# lupa-hdmi-carrier.net
KiCad netlist of a schematic drawn in EAGLE
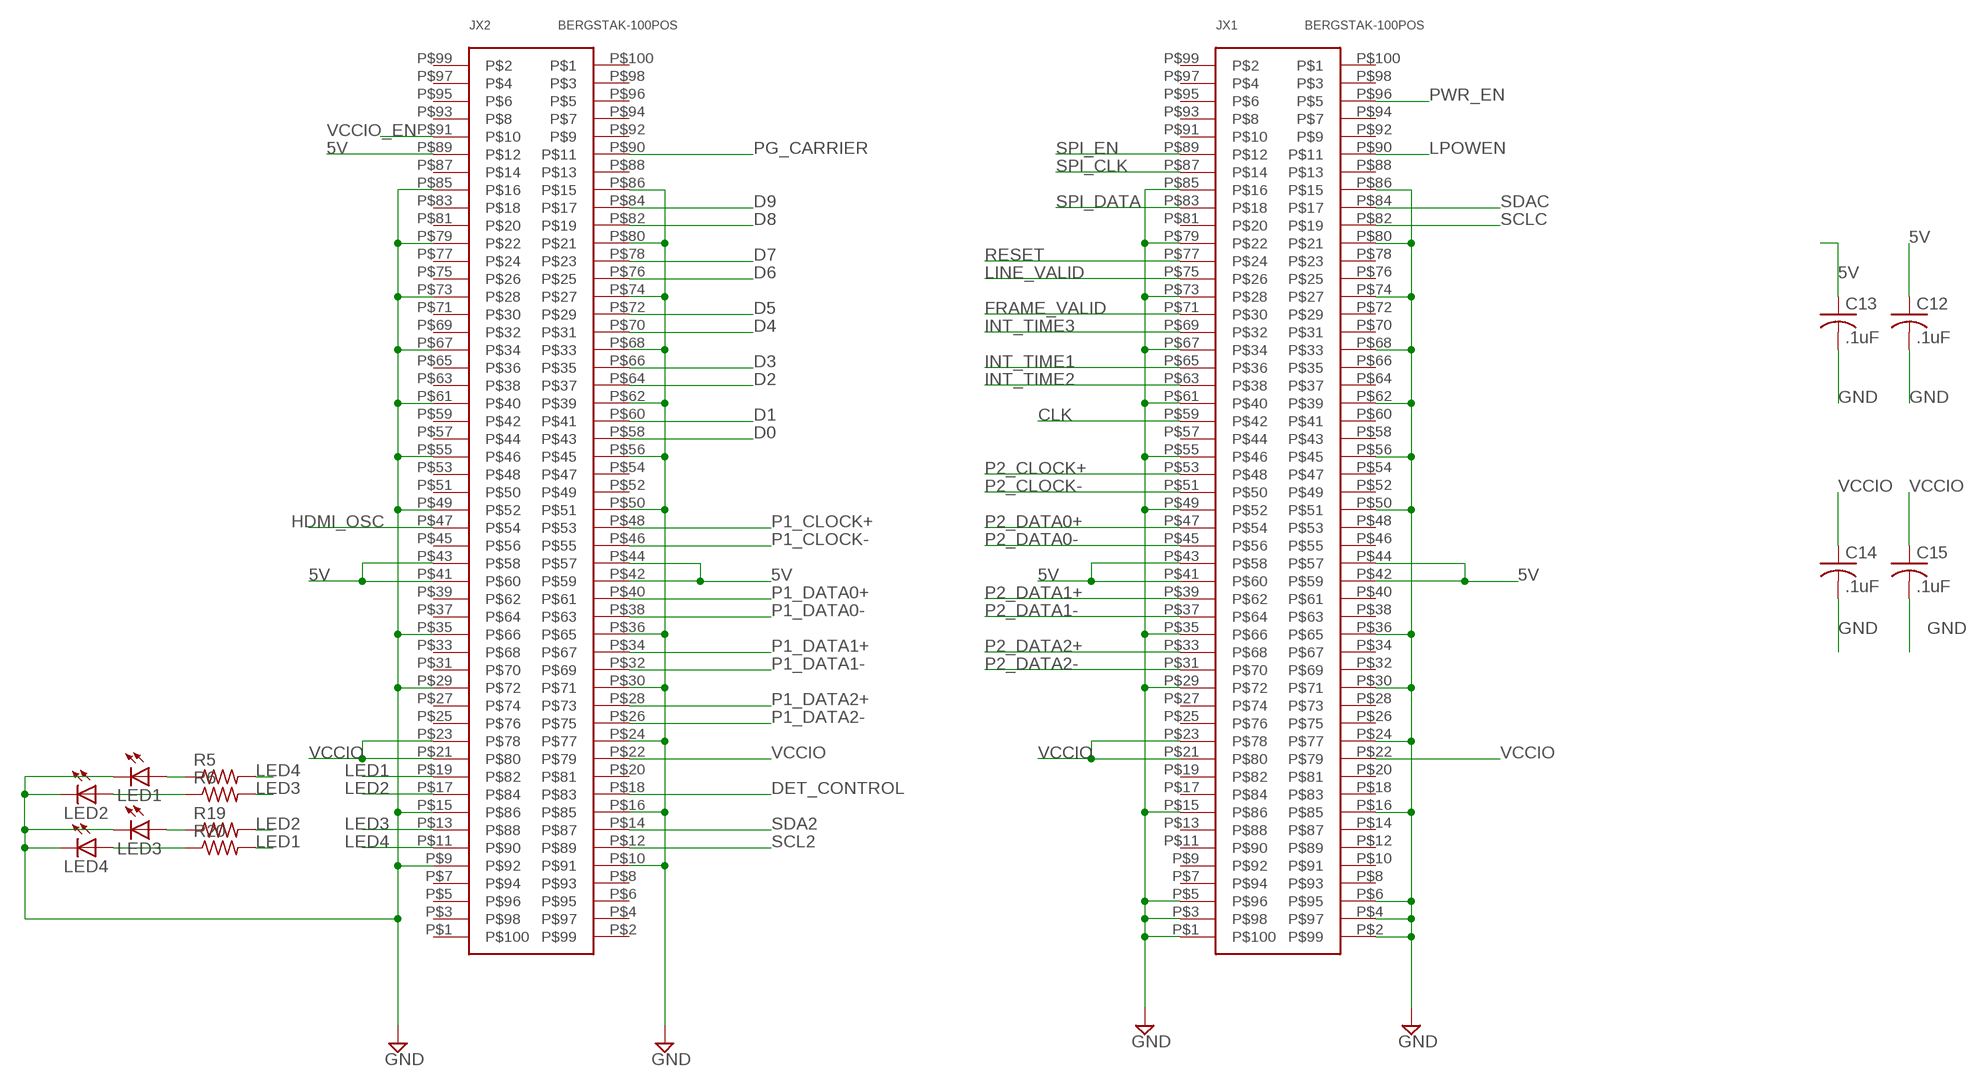
[diagram p0: schematic, sheet 1]
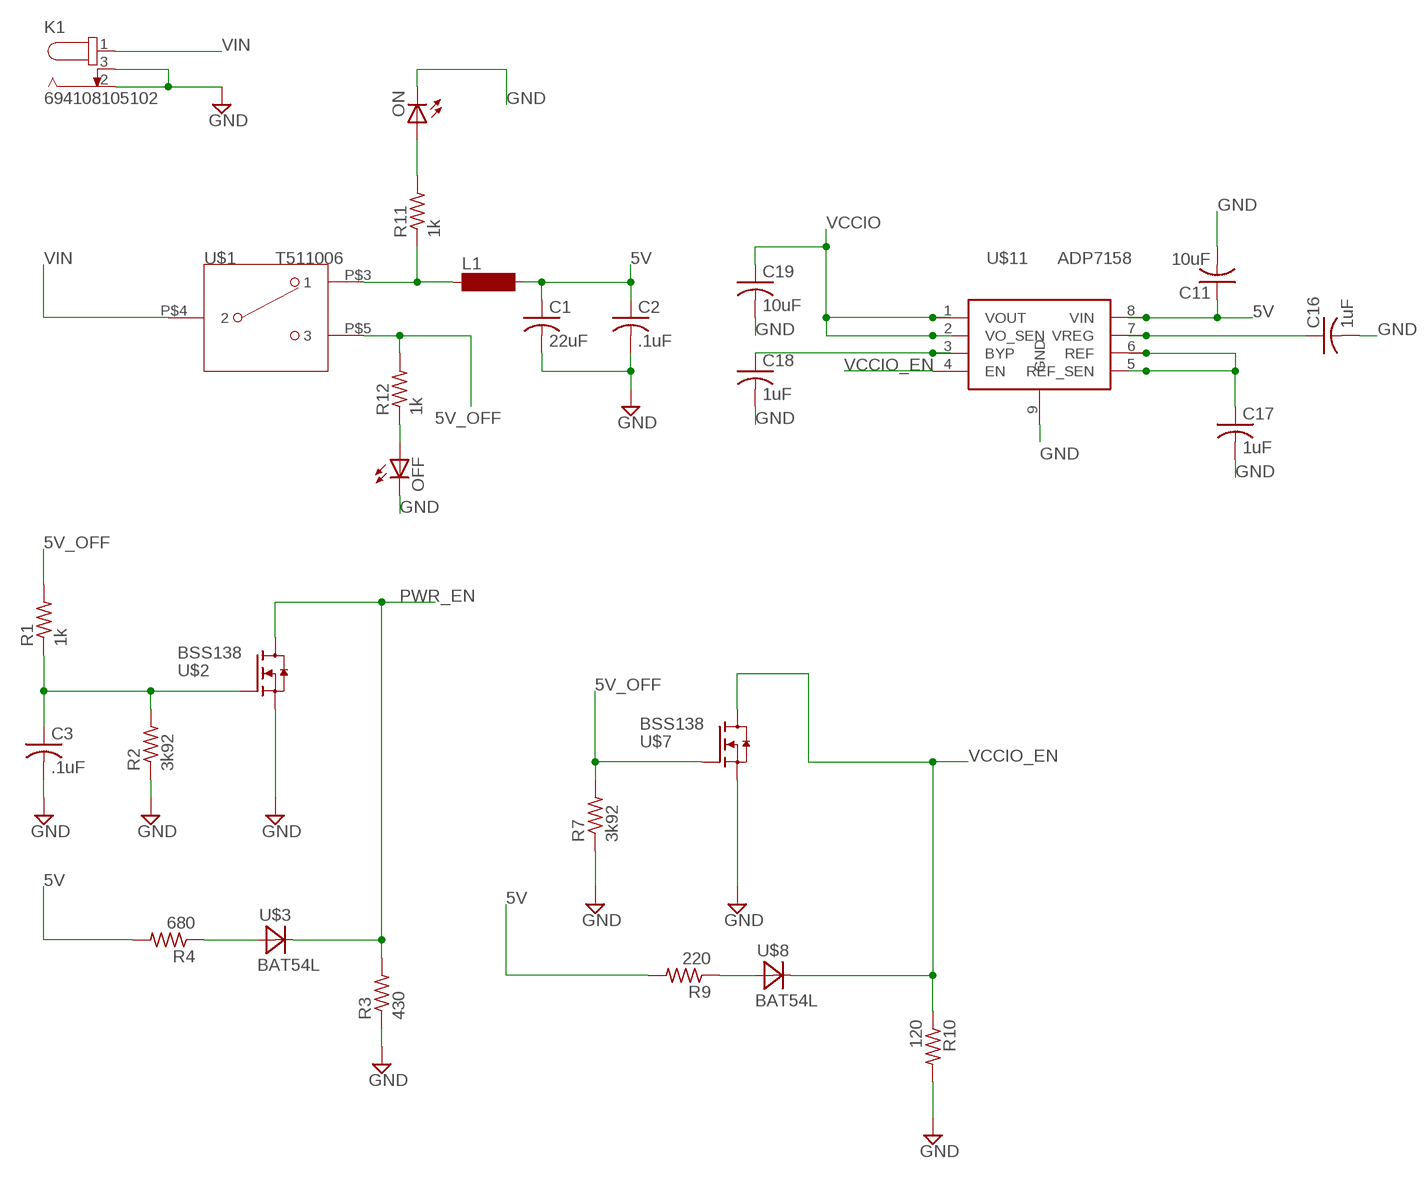
[diagram p1: schematic, sheet 2]
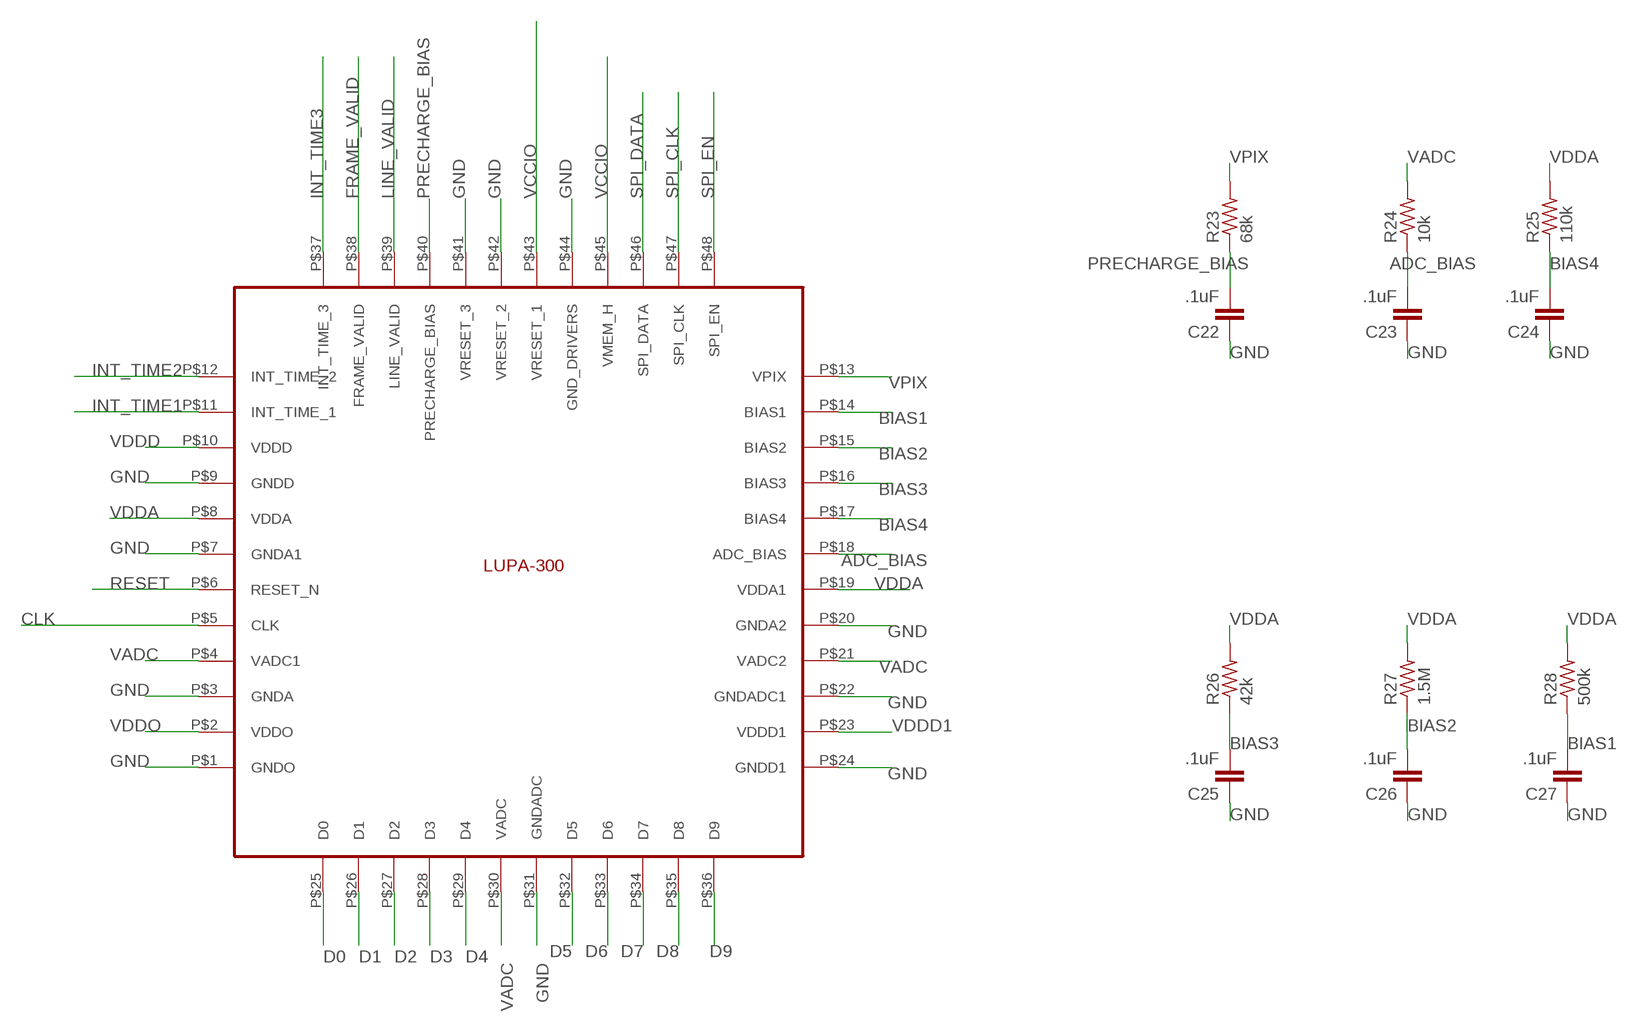
[diagram p2: schematic, sheet 3]
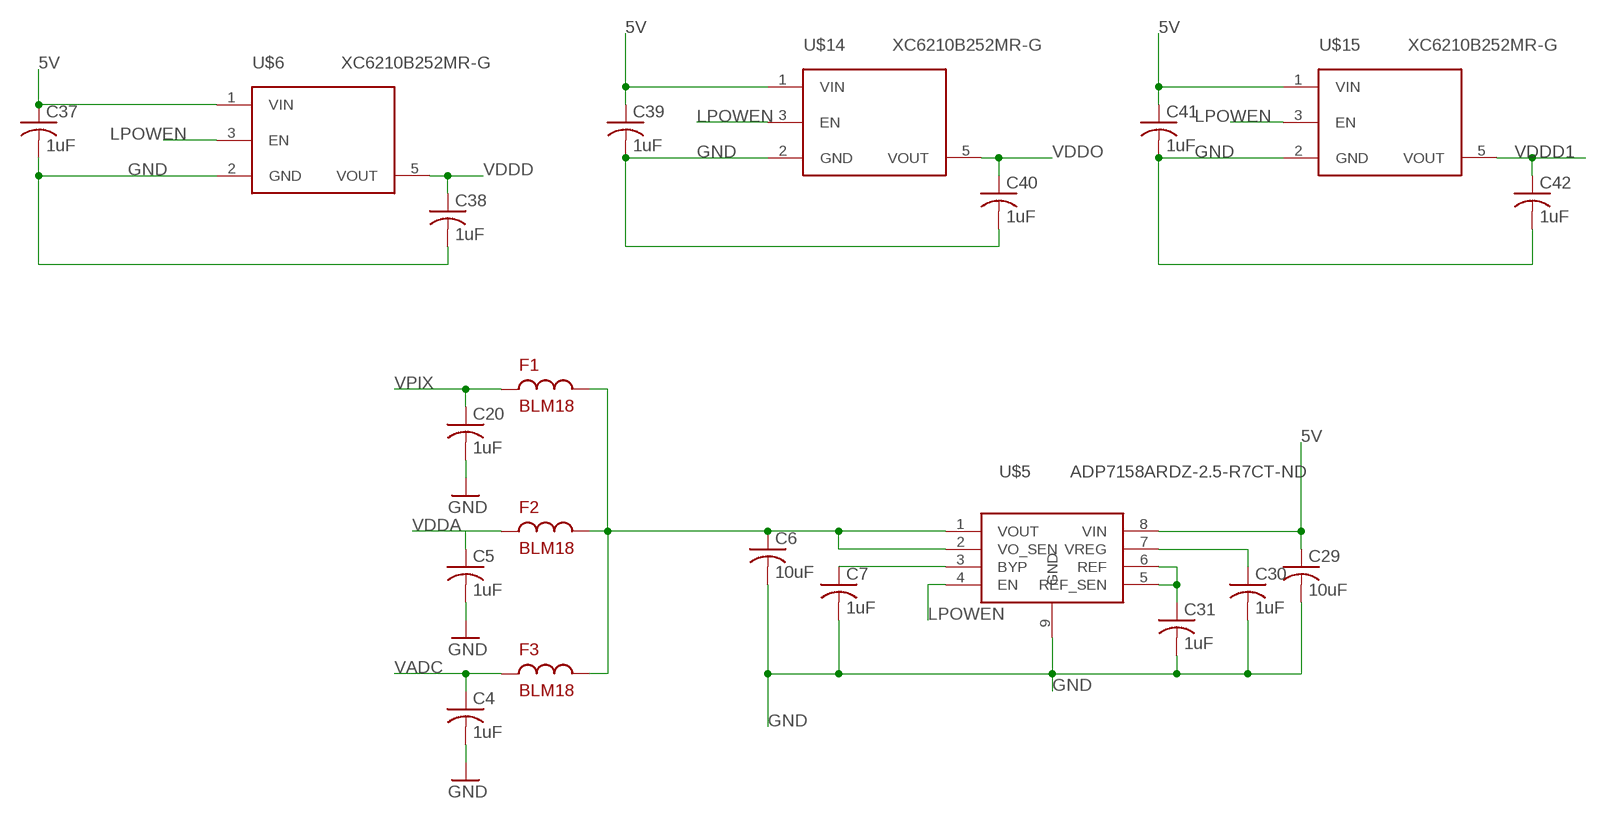
[diagram p3: schematic, sheet 4]
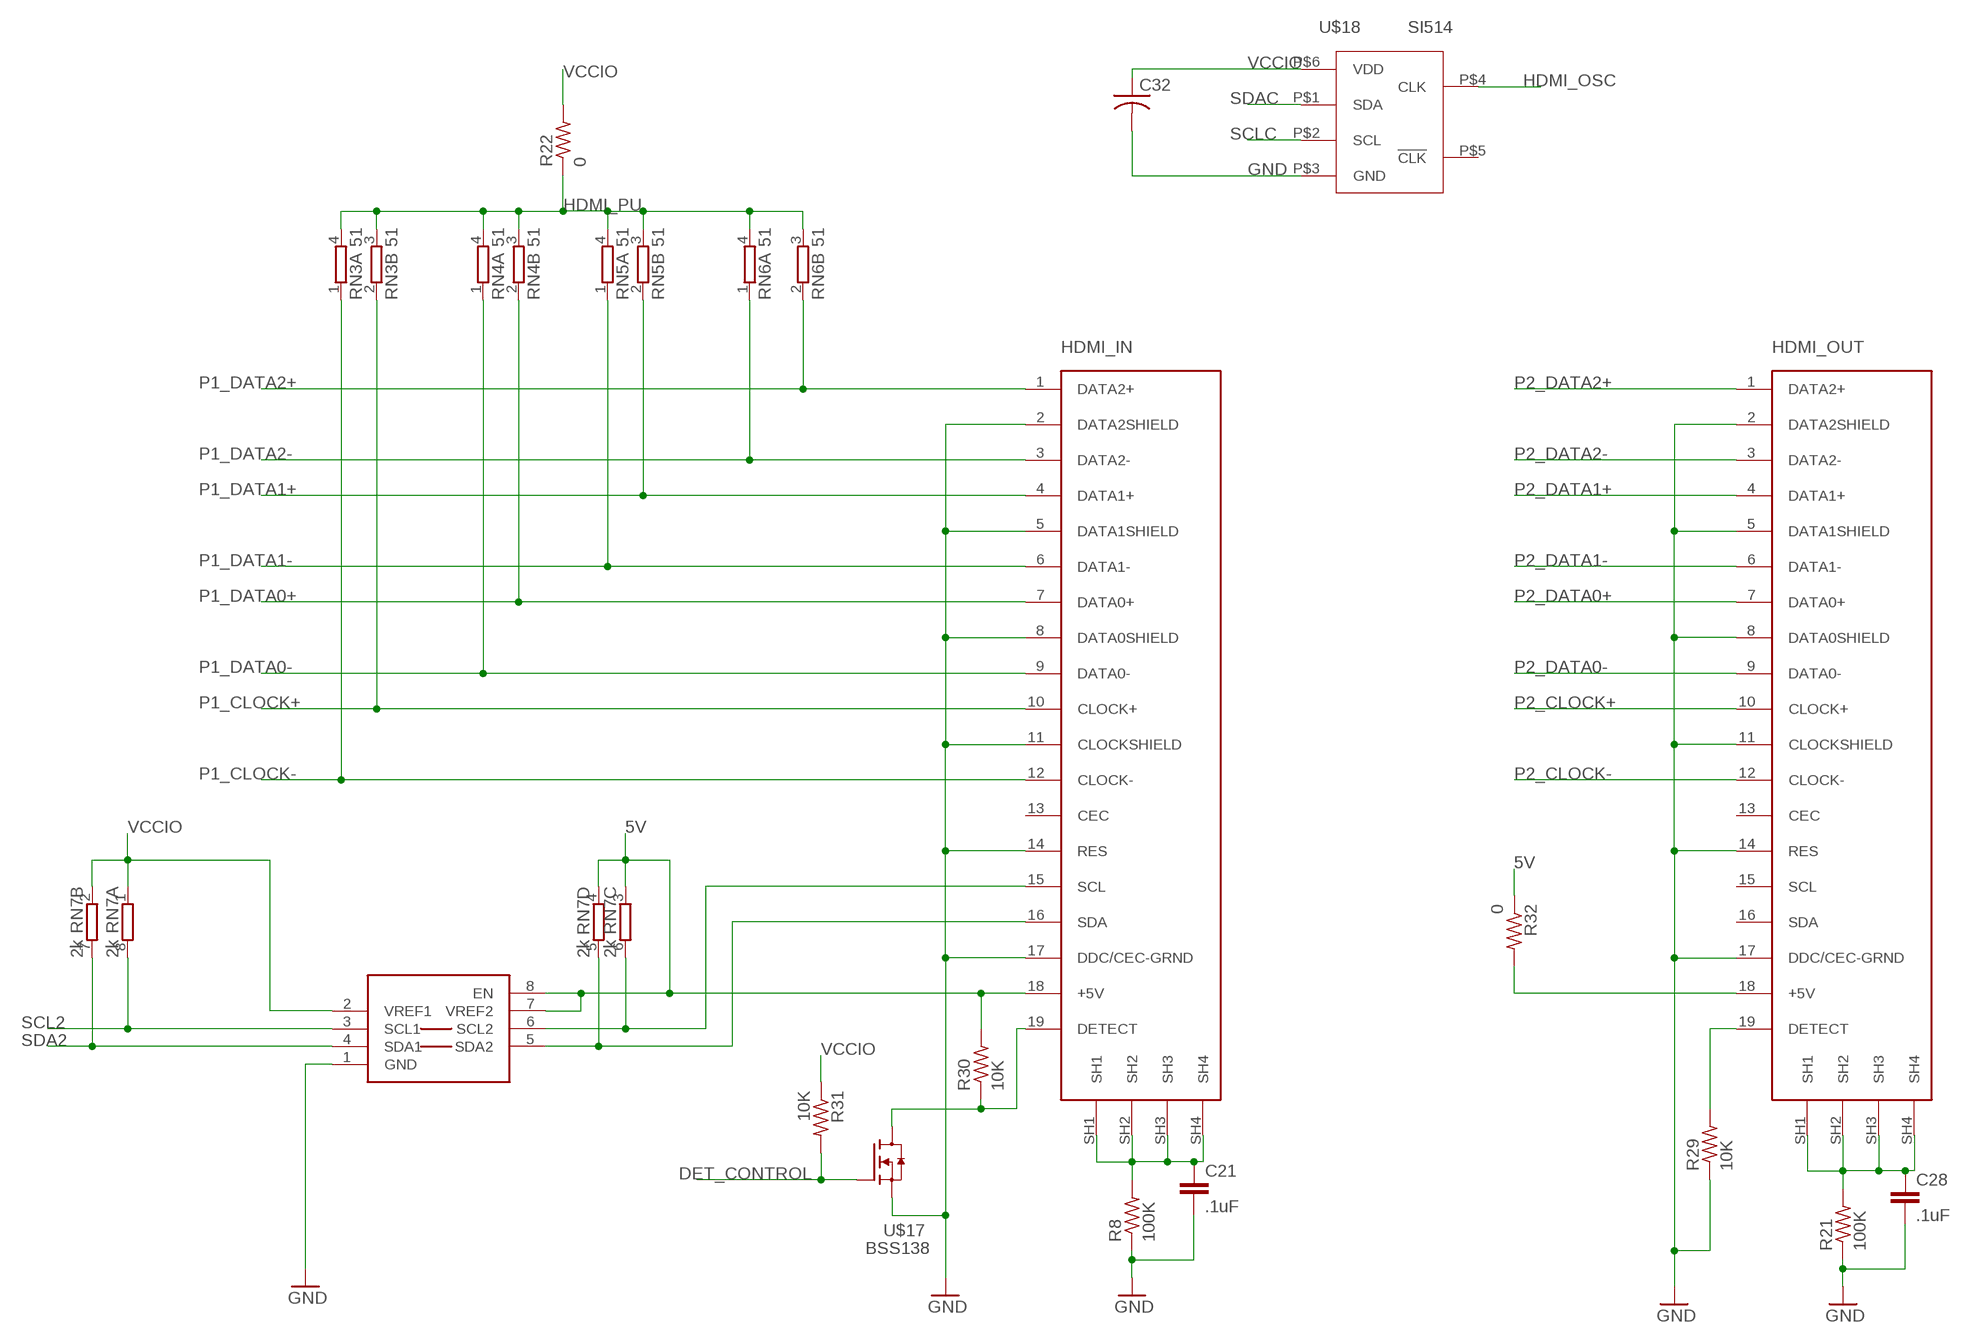
[diagram p4: schematic, sheet 5]

(export (version "E")
  (design (tool "Eeschema 10.0.6"))
  (components
    (comp (ref "C4")
      (value "1uF")
      (footprint "eagle-import:C0603")
      (libsource (lib "eagle-import") (part "C-USC0603"))
    )
    (comp (ref "C5")
      (value "1uF")
      (footprint "eagle-import:C0603")
      (libsource (lib "eagle-import") (part "C-USC0603"))
    )
    (comp (ref "C6")
      (value "10uF")
      (footprint "eagle-import:C0603")
      (libsource (lib "eagle-import") (part "C-USC0603"))
    )
    (comp (ref "C7")
      (value "1uF")
      (footprint "eagle-import:C0603")
      (libsource (lib "eagle-import") (part "C-USC0603"))
    )
    (comp (ref "C20")
      (value "1uF")
      (footprint "eagle-import:C0603")
      (libsource (lib "eagle-import") (part "C-USC0603"))
    )
    (comp (ref "C29")
      (value "10uF")
      (footprint "eagle-import:C0603")
      (libsource (lib "eagle-import") (part "C-USC0603"))
    )
    (comp (ref "C30")
      (value "1uF")
      (footprint "eagle-import:C0603")
      (libsource (lib "eagle-import") (part "C-USC0603"))
    )
    (comp (ref "C31")
      (value "1uF")
      (footprint "eagle-import:C0603")
      (libsource (lib "eagle-import") (part "C-USC0603"))
    )
    (comp (ref "C37")
      (value "1uF")
      (footprint "eagle-import:C0603")
      (libsource (lib "eagle-import") (part "C-USC0603"))
    )
    (comp (ref "C38")
      (value "1uF")
      (footprint "eagle-import:C0603")
      (libsource (lib "eagle-import") (part "C-USC0603"))
    )
    (comp (ref "C39")
      (value "1uF")
      (footprint "eagle-import:C0603")
      (libsource (lib "eagle-import") (part "C-USC0603"))
    )
    (comp (ref "C40")
      (value "1uF")
      (footprint "eagle-import:C0603")
      (libsource (lib "eagle-import") (part "C-USC0603"))
    )
    (comp (ref "C41")
      (value "1uF")
      (footprint "eagle-import:C0603")
      (libsource (lib "eagle-import") (part "C-USC0603"))
    )
    (comp (ref "C42")
      (value "1uF")
      (footprint "eagle-import:C0603")
      (libsource (lib "eagle-import") (part "C-USC0603"))
    )
    (comp (ref "F1")
      (value "BLM18")
      (footprint "eagle-import:C0603K")
      (libsource (lib "eagle-import") (part "BLM18"))
    )
    (comp (ref "F2")
      (value "BLM18")
      (footprint "eagle-import:C0603K")
      (libsource (lib "eagle-import") (part "BLM18"))
    )
    (comp (ref "F3")
      (value "BLM18")
      (footprint "eagle-import:C0603K")
      (libsource (lib "eagle-import") (part "BLM18"))
    )
    (comp (ref "U$5")
      (value "ADP7158ARDZ-2.5-R7CT-ND")
      (footprint "eagle-import:SO08")
      (libsource (lib "eagle-import") (part "ADP7158ARDZ-2.5-R7CT-ND"))
    )
    (comp (ref "U$6")
      (value "XC6210B252MR-G")
      (footprint "eagle-import:SOT25")
      (libsource (lib "eagle-import") (part "XC6210B252MR-G"))
    )
    (comp (ref "U$14")
      (value "XC6210B252MR-G")
      (footprint "eagle-import:SOT25")
      (libsource (lib "eagle-import") (part "XC6210B252MR-G"))
    )
    (comp (ref "U$15")
      (value "XC6210B252MR-G")
      (footprint "eagle-import:SOT25")
      (libsource (lib "eagle-import") (part "XC6210B252MR-G"))
    )
    (comp (ref "C1")
      (value "22uF")
      (footprint "eagle-import:C1206")
      (libsource (lib "eagle-import") (part "C-USC1206"))
    )
    (comp (ref "C2")
      (value ".1uF")
      (footprint "eagle-import:C0603")
      (libsource (lib "eagle-import") (part "C-USC0603"))
    )
    (comp (ref "C3")
      (value ".1uF")
      (footprint "eagle-import:C0603")
      (libsource (lib "eagle-import") (part "C-USC0603"))
    )
    (comp (ref "C11")
      (value "10uF")
      (footprint "eagle-import:C0603")
      (libsource (lib "eagle-import") (part "C-USC0603"))
    )
    (comp (ref "C16")
      (value "1uF")
      (footprint "eagle-import:C0603")
      (libsource (lib "eagle-import") (part "C-USC0603"))
    )
    (comp (ref "C17")
      (value "1uF")
      (footprint "eagle-import:C0603")
      (libsource (lib "eagle-import") (part "C-USC0603"))
    )
    (comp (ref "C18")
      (value "1uF")
      (footprint "eagle-import:C0603")
      (libsource (lib "eagle-import") (part "C-USC0603"))
    )
    (comp (ref "C19")
      (value "10uF")
      (footprint "eagle-import:C0603")
      (libsource (lib "eagle-import") (part "C-USC0603"))
    )
    (comp (ref "K1")
      (value "694108105102")
      (footprint "eagle-import:694108105102")
      (libsource (lib "eagle-import") (part "694108105102"))
    )
    (comp (ref "L1")
      (value "MS85")
      (footprint "eagle-import:MS85")
      (libsource (lib "eagle-import") (part "MS85"))
    )
    (comp (ref "OFF")
      (value "LEDCHIPLED_0805")
      (footprint "eagle-import:CHIPLED_0805")
      (libsource (lib "eagle-import") (part "LEDCHIPLED_0805"))
    )
    (comp (ref "ON")
      (value "LEDCHIPLED_0805")
      (footprint "eagle-import:CHIPLED_0805")
      (libsource (lib "eagle-import") (part "LEDCHIPLED_0805"))
    )
    (comp (ref "R1")
      (value "1k")
      (footprint "eagle-import:R0603")
      (libsource (lib "eagle-import") (part "rcl_334_R-US_R0603"))
    )
    (comp (ref "R2")
      (value "3k92")
      (footprint "eagle-import:R0603")
      (libsource (lib "eagle-import") (part "rcl_334_R-US_R0603"))
    )
    (comp (ref "R3")
      (value "430")
      (footprint "eagle-import:R0603")
      (libsource (lib "eagle-import") (part "rcl_334_R-US_R0603"))
    )
    (comp (ref "R4")
      (value "680")
      (footprint "eagle-import:R0603")
      (libsource (lib "eagle-import") (part "rcl_334_R-US_R0603"))
    )
    (comp (ref "R7")
      (value "3k92")
      (footprint "eagle-import:R0603")
      (libsource (lib "eagle-import") (part "rcl_334_R-US_R0603"))
    )
    (comp (ref "R9")
      (value "220")
      (footprint "eagle-import:R0603")
      (libsource (lib "eagle-import") (part "rcl_334_R-US_R0603"))
    )
    (comp (ref "R10")
      (value "120")
      (footprint "eagle-import:R0603")
      (libsource (lib "eagle-import") (part "rcl_334_R-US_R0603"))
    )
    (comp (ref "R11")
      (value "1k")
      (footprint "eagle-import:R0603")
      (libsource (lib "eagle-import") (part "rcl_334_R-US_R0603"))
    )
    (comp (ref "R12")
      (value "1k")
      (footprint "eagle-import:R0603")
      (libsource (lib "eagle-import") (part "rcl_334_R-US_R0603"))
    )
    (comp (ref "U$1")
      (value "T511006")
      (footprint "eagle-import:SPDT")
      (libsource (lib "eagle-import") (part "T511006"))
    )
    (comp (ref "U$2")
      (value "BSS138")
      (footprint "eagle-import:SOT23")
      (libsource (lib "eagle-import") (part "BSS138"))
    )
    (comp (ref "U$3")
      (value "BAT54L")
      (footprint "eagle-import:SOT23")
      (libsource (lib "eagle-import") (part "BAT54L"))
    )
    (comp (ref "U$7")
      (value "BSS138")
      (footprint "eagle-import:SOT23")
      (libsource (lib "eagle-import") (part "BSS138"))
    )
    (comp (ref "U$8")
      (value "BAT54L")
      (footprint "eagle-import:SOT23")
      (libsource (lib "eagle-import") (part "BAT54L"))
    )
    (comp (ref "U$11")
      (value "ADP7158")
      (footprint "eagle-import:SO08")
      (libsource (lib "eagle-import") (part "ADP7158"))
    )
    (comp (ref "C21")
      (value ".1uF")
      (footprint "eagle-import:C0603K")
      (libsource (lib "eagle-import") (part "C-EUC0603K"))
    )
    (comp (ref "C28")
      (value ".1uF")
      (footprint "eagle-import:C0603K")
      (libsource (lib "eagle-import") (part "C-EUC0603K"))
    )
    (comp (ref "C32")
      (value "C-USC0603")
      (footprint "eagle-import:C0603")
      (libsource (lib "eagle-import") (part "C-USC0603"))
    )
    (comp (ref "HDMI_IN")
      (value "HDMI-TYPE-A-RECEPTICALFCI10029449")
      (footprint "eagle-import:FCI-HDMI-TYPE-A-RECEPT")
      (libsource (lib "eagle-import") (part "HDMI-TYPE-A-RECEPTICALFCI10029449"))
    )
    (comp (ref "HDMI_OUT")
      (value "HDMI-TYPE-A-RECEPTICALFCI10029449")
      (footprint "eagle-import:FCI-HDMI-TYPE-A-RECEPT")
      (libsource (lib "eagle-import") (part "HDMI-TYPE-A-RECEPTICALFCI10029449"))
    )
    (comp (ref "PCA9306")
      (value "PCA9306")
      (footprint "eagle-import:PSOP-8")
      (libsource (lib "eagle-import") (part "PCA9306"))
    )
    (comp (ref "R8")
      (value "100K")
      (footprint "eagle-import:R0603")
      (libsource (lib "eagle-import") (part "R-US_R0603"))
    )
    (comp (ref "R21")
      (value "100K")
      (footprint "eagle-import:R0603")
      (libsource (lib "eagle-import") (part "R-US_R0603"))
    )
    (comp (ref "R22")
      (value "0")
      (footprint "eagle-import:R0603")
      (libsource (lib "eagle-import") (part "rcl_334_R-US_R0603"))
    )
    (comp (ref "R29")
      (value "10K")
      (footprint "eagle-import:R0603")
      (libsource (lib "eagle-import") (part "R-US_R0603"))
    )
    (comp (ref "R30")
      (value "10K")
      (footprint "eagle-import:R0603")
      (libsource (lib "eagle-import") (part "R-US_R0603"))
    )
    (comp (ref "R31")
      (value "10K")
      (footprint "eagle-import:R0603")
      (libsource (lib "eagle-import") (part "R-US_R0603"))
    )
    (comp (ref "R32")
      (value "0")
      (footprint "eagle-import:R0603")
      (libsource (lib "eagle-import") (part "R-US_R0603"))
    )
    (comp (ref "RN3")
      (value "51")
      (footprint "eagle-import:EXB34V")
      (libsource (lib "eagle-import") (part "2R-NEXB34V"))
    )
    (comp (ref "RN4")
      (value "51")
      (footprint "eagle-import:EXB34V")
      (libsource (lib "eagle-import") (part "2R-NEXB34V"))
    )
    (comp (ref "RN5")
      (value "51")
      (footprint "eagle-import:EXB34V")
      (libsource (lib "eagle-import") (part "2R-NEXB34V"))
    )
    (comp (ref "RN6")
      (value "51")
      (footprint "eagle-import:EXB34V")
      (libsource (lib "eagle-import") (part "2R-NEXB34V"))
    )
    (comp (ref "RN7")
      (value "2k")
      (footprint "eagle-import:0603-ARV")
      (libsource (lib "eagle-import") (part "4R-N0603-ARV"))
    )
    (comp (ref "U$17")
      (value "BSS138")
      (footprint "eagle-import:SOT23")
      (libsource (lib "eagle-import") (part "BSS138"))
    )
    (comp (ref "U$18")
      (value "SI514")
      (footprint "eagle-import:XTAL-6PIN")
      (libsource (lib "eagle-import") (part "SI514"))
    )
    (comp (ref "C12")
      (value ".1uF")
      (footprint "eagle-import:C0603")
      (libsource (lib "eagle-import") (part "C-USC0603"))
    )
    (comp (ref "C13")
      (value ".1uF")
      (footprint "eagle-import:C0603")
      (libsource (lib "eagle-import") (part "C-USC0603"))
    )
    (comp (ref "C14")
      (value ".1uF")
      (footprint "eagle-import:C0603")
      (libsource (lib "eagle-import") (part "C-USC0603"))
    )
    (comp (ref "C15")
      (value ".1uF")
      (footprint "eagle-import:C0603")
      (libsource (lib "eagle-import") (part "C-USC0603"))
    )
    (comp (ref "JX1")
      (value "BERGSTAK-100POS")
      (footprint "eagle-import:BERG100POS")
      (libsource (lib "eagle-import") (part "BERGSTAK-100POS"))
    )
    (comp (ref "JX2")
      (value "BERGSTAK-100POS")
      (footprint "eagle-import:BERG100POS")
      (libsource (lib "eagle-import") (part "BERGSTAK-100POS"))
    )
    (comp (ref "LED1")
      (value "LEDCHIPLED_0805")
      (footprint "eagle-import:CHIPLED_0805")
      (libsource (lib "eagle-import") (part "led_259_LEDCHIPLED_0805"))
    )
    (comp (ref "LED2")
      (value "LEDCHIPLED_0805")
      (footprint "eagle-import:CHIPLED_0805")
      (libsource (lib "eagle-import") (part "led_259_LEDCHIPLED_0805"))
    )
    (comp (ref "LED3")
      (value "LEDCHIPLED_0805")
      (footprint "eagle-import:CHIPLED_0805")
      (libsource (lib "eagle-import") (part "led_259_LEDCHIPLED_0805"))
    )
    (comp (ref "LED4")
      (value "LEDCHIPLED_0805")
      (footprint "eagle-import:CHIPLED_0805")
      (libsource (lib "eagle-import") (part "led_259_LEDCHIPLED_0805"))
    )
    (comp (ref "R5")
      (value "R-US_R0603")
      (footprint "eagle-import:R0603")
      (libsource (lib "eagle-import") (part "resistor_348_R-US_R0603"))
    )
    (comp (ref "R6")
      (value "R-US_R0603")
      (footprint "eagle-import:R0603")
      (libsource (lib "eagle-import") (part "resistor_348_R-US_R0603"))
    )
    (comp (ref "R19")
      (value "R-US_R0603")
      (footprint "eagle-import:R0603")
      (libsource (lib "eagle-import") (part "resistor_348_R-US_R0603"))
    )
    (comp (ref "R20")
      (value "R-US_R0603")
      (footprint "eagle-import:R0603")
      (libsource (lib "eagle-import") (part "resistor_348_R-US_R0603"))
    )
    (comp (ref "C22")
      (value ".1uF")
      (footprint "eagle-import:C0603")
      (libsource (lib "eagle-import") (part "rcl_334_C-EUC0603"))
    )
    (comp (ref "C23")
      (value ".1uF")
      (footprint "eagle-import:C0603")
      (libsource (lib "eagle-import") (part "rcl_334_C-EUC0603"))
    )
    (comp (ref "C24")
      (value ".1uF")
      (footprint "eagle-import:C0603")
      (libsource (lib "eagle-import") (part "rcl_334_C-EUC0603"))
    )
    (comp (ref "C25")
      (value ".1uF")
      (footprint "eagle-import:C0603")
      (libsource (lib "eagle-import") (part "rcl_334_C-EUC0603"))
    )
    (comp (ref "C26")
      (value ".1uF")
      (footprint "eagle-import:C0603")
      (libsource (lib "eagle-import") (part "rcl_334_C-EUC0603"))
    )
    (comp (ref "C27")
      (value ".1uF")
      (footprint "eagle-import:C0603")
      (libsource (lib "eagle-import") (part "rcl_334_C-EUC0603"))
    )
    (comp (ref "R23")
      (value "68k")
      (footprint "eagle-import:R0603")
      (libsource (lib "eagle-import") (part "rcl_334_R-US_R0603"))
    )
    (comp (ref "R24")
      (value "10k")
      (footprint "eagle-import:R0603")
      (libsource (lib "eagle-import") (part "rcl_334_R-US_R0603"))
    )
    (comp (ref "R25")
      (value "110k")
      (footprint "eagle-import:R0603")
      (libsource (lib "eagle-import") (part "rcl_334_R-US_R0603"))
    )
    (comp (ref "R26")
      (value "42k")
      (footprint "eagle-import:R0603")
      (libsource (lib "eagle-import") (part "rcl_334_R-US_R0603"))
    )
    (comp (ref "R27")
      (value "1.5M")
      (footprint "eagle-import:R0603")
      (libsource (lib "eagle-import") (part "rcl_334_R-US_R0603"))
    )
    (comp (ref "R28")
      (value "500k")
      (footprint "eagle-import:R0603")
      (libsource (lib "eagle-import") (part "rcl_334_R-US_R0603"))
    )
    (comp (ref "U$4")
      (value "LUPA300")
      (footprint "eagle-import:LUPA300")
      (libsource (lib "eagle-import") (part "LUPA300"))
    )
  )
  (nets
    (net (code "1") (name "5V") (class "Default")
      (node (ref "C1") (pin "1") (pinfunction "1_1") (pintype "passive"))
      (node (ref "C11") (pin "1") (pinfunction "1_1") (pintype "passive"))
      (node (ref "C12") (pin "1") (pinfunction "1_1") (pintype "passive"))
      (node (ref "C13") (pin "1") (pinfunction "1_1") (pintype "passive"))
      (node (ref "C2") (pin "1") (pinfunction "1_1") (pintype "passive"))
      (node (ref "C29") (pin "1") (pinfunction "1_1") (pintype "passive"))
      (node (ref "C37") (pin "1") (pinfunction "1_1") (pintype "passive"))
      (node (ref "C39") (pin "1") (pinfunction "1_1") (pintype "passive"))
      (node (ref "C41") (pin "1") (pinfunction "1_1") (pintype "passive"))
      (node (ref "HDMI_IN") (pin "18") (pinfunction "+5V_18") (pintype "bidirectional"))
      (node (ref "JX1") (pin "P$41") (pinfunction "P$60_P$41") (pintype "bidirectional"))
      (node (ref "JX1") (pin "P$42") (pinfunction "P$59_P$42") (pintype "bidirectional"))
      (node (ref "JX1") (pin "P$43") (pinfunction "P$58_P$43") (pintype "bidirectional"))
      (node (ref "JX1") (pin "P$44") (pinfunction "P$57_P$44") (pintype "bidirectional"))
      (node (ref "JX2") (pin "P$41") (pinfunction "P$60_P$41") (pintype "bidirectional"))
      (node (ref "JX2") (pin "P$42") (pinfunction "P$59_P$42") (pintype "bidirectional"))
      (node (ref "JX2") (pin "P$43") (pinfunction "P$58_P$43") (pintype "bidirectional"))
      (node (ref "JX2") (pin "P$44") (pinfunction "P$57_P$44") (pintype "bidirectional"))
      (node (ref "JX2") (pin "P$89") (pinfunction "P$12_P$89") (pintype "bidirectional"))
      (node (ref "L1") (pin "2") (pinfunction "2_2") (pintype "passive"))
      (node (ref "PCA9306") (pin "7") (pinfunction "VREF2_7") (pintype "bidirectional"))
      (node (ref "PCA9306") (pin "8") (pinfunction "EN_8") (pintype "bidirectional"))
      (node (ref "R30") (pin "2") (pinfunction "2_2") (pintype "passive"))
      (node (ref "R32") (pin "1") (pinfunction "1_1") (pintype "passive"))
      (node (ref "R4") (pin "2") (pinfunction "2_2") (pintype "passive"))
      (node (ref "R9") (pin "2") (pinfunction "2_2") (pintype "passive"))
      (node (ref "RN7") (pin "3") (pinfunction "1_3") (pintype "passive"))
      (node (ref "RN7") (pin "4") (pinfunction "1_4") (pintype "passive"))
      (node (ref "U$11") (pin "8") (pinfunction "VIN_8") (pintype "bidirectional"))
      (node (ref "U$14") (pin "1") (pinfunction "VIN_1") (pintype "bidirectional"))
      (node (ref "U$15") (pin "1") (pinfunction "VIN_1") (pintype "bidirectional"))
      (node (ref "U$5") (pin "8") (pinfunction "VIN_8") (pintype "bidirectional"))
      (node (ref "U$6") (pin "1") (pinfunction "VIN_1") (pintype "bidirectional"))
    )
    (net (code "2") (name "5V_OFF") (class "Default")
      (node (ref "R1") (pin "2") (pinfunction "2_2") (pintype "passive"))
      (node (ref "R12") (pin "2") (pinfunction "2_2") (pintype "passive"))
      (node (ref "R7") (pin "2") (pinfunction "2_2") (pintype "passive"))
      (node (ref "U$1") (pin "P$5") (pinfunction "3_P$5") (pintype "bidirectional"))
      (node (ref "U$7") (pin "1") (pinfunction "G_1") (pintype "passive"))
    )
    (net (code "3") (name "ADC_BIAS") (class "Default")
      (node (ref "C23") (pin "2") (pinfunction "2_2") (pintype "passive"))
      (node (ref "R24") (pin "1") (pinfunction "1_1") (pintype "passive"))
      (node (ref "U$4") (pin "P$18") (pinfunction "ADC_BIAS_P$18") (pintype "bidirectional"))
    )
    (net (code "4") (name "BIAS1") (class "Default")
      (node (ref "C27") (pin "2") (pinfunction "2_2") (pintype "passive"))
      (node (ref "R28") (pin "1") (pinfunction "1_1") (pintype "passive"))
      (node (ref "U$4") (pin "P$14") (pinfunction "BIAS1_P$14") (pintype "bidirectional"))
    )
    (net (code "5") (name "BIAS2") (class "Default")
      (node (ref "C26") (pin "2") (pinfunction "2_2") (pintype "passive"))
      (node (ref "R27") (pin "1") (pinfunction "1_1") (pintype "passive"))
      (node (ref "U$4") (pin "P$15") (pinfunction "BIAS2_P$15") (pintype "bidirectional"))
    )
    (net (code "6") (name "BIAS3") (class "Default")
      (node (ref "C25") (pin "2") (pinfunction "2_2") (pintype "passive"))
      (node (ref "R26") (pin "1") (pinfunction "1_1") (pintype "passive"))
      (node (ref "U$4") (pin "P$16") (pinfunction "BIAS3_P$16") (pintype "bidirectional"))
    )
    (net (code "7") (name "BIAS4") (class "Default")
      (node (ref "C24") (pin "2") (pinfunction "2_2") (pintype "passive"))
      (node (ref "R25") (pin "1") (pinfunction "1_1") (pintype "passive"))
      (node (ref "U$4") (pin "P$17") (pinfunction "BIAS4_P$17") (pintype "bidirectional"))
    )
    (net (code "8") (name "CLK") (class "Default")
      (node (ref "JX1") (pin "P$59") (pinfunction "P$42_P$59") (pintype "bidirectional"))
      (node (ref "U$4") (pin "P$5") (pinfunction "CLK_P$5") (pintype "bidirectional"))
    )
    (net (code "9") (name "D0") (class "Default")
      (node (ref "JX2") (pin "P$58") (pinfunction "P$43_P$58") (pintype "bidirectional"))
      (node (ref "U$4") (pin "P$25") (pinfunction "D0_P$25") (pintype "bidirectional"))
    )
    (net (code "10") (name "D1") (class "Default")
      (node (ref "JX2") (pin "P$60") (pinfunction "P$41_P$60") (pintype "bidirectional"))
      (node (ref "U$4") (pin "P$26") (pinfunction "D1_P$26") (pintype "bidirectional"))
    )
    (net (code "11") (name "D2") (class "Default")
      (node (ref "JX2") (pin "P$64") (pinfunction "P$37_P$64") (pintype "bidirectional"))
      (node (ref "U$4") (pin "P$27") (pinfunction "D2_P$27") (pintype "bidirectional"))
    )
    (net (code "12") (name "D3") (class "Default")
      (node (ref "JX2") (pin "P$66") (pinfunction "P$35_P$66") (pintype "bidirectional"))
      (node (ref "U$4") (pin "P$28") (pinfunction "D3_P$28") (pintype "bidirectional"))
    )
    (net (code "13") (name "D4") (class "Default")
      (node (ref "JX2") (pin "P$70") (pinfunction "P$31_P$70") (pintype "bidirectional"))
      (node (ref "U$4") (pin "P$29") (pinfunction "D4_P$29") (pintype "bidirectional"))
    )
    (net (code "14") (name "D5") (class "Default")
      (node (ref "JX2") (pin "P$72") (pinfunction "P$29_P$72") (pintype "bidirectional"))
      (node (ref "U$4") (pin "P$32") (pinfunction "D5_P$32") (pintype "bidirectional"))
    )
    (net (code "15") (name "D6") (class "Default")
      (node (ref "JX2") (pin "P$76") (pinfunction "P$25_P$76") (pintype "bidirectional"))
      (node (ref "U$4") (pin "P$33") (pinfunction "D6_P$33") (pintype "bidirectional"))
    )
    (net (code "16") (name "D7") (class "Default")
      (node (ref "JX2") (pin "P$78") (pinfunction "P$23_P$78") (pintype "bidirectional"))
      (node (ref "U$4") (pin "P$34") (pinfunction "D7_P$34") (pintype "bidirectional"))
    )
    (net (code "17") (name "D8") (class "Default")
      (node (ref "JX2") (pin "P$82") (pinfunction "P$19_P$82") (pintype "bidirectional"))
      (node (ref "U$4") (pin "P$35") (pinfunction "D8_P$35") (pintype "bidirectional"))
    )
    (net (code "18") (name "D9") (class "Default")
      (node (ref "JX2") (pin "P$84") (pinfunction "P$17_P$84") (pintype "bidirectional"))
      (node (ref "U$4") (pin "P$36") (pinfunction "D9_P$36") (pintype "bidirectional"))
    )
    (net (code "19") (name "DET_CONTROL") (class "Default")
      (node (ref "JX2") (pin "P$18") (pinfunction "P$83_P$18") (pintype "bidirectional"))
      (node (ref "R31") (pin "2") (pinfunction "2_2") (pintype "passive"))
      (node (ref "U$17") (pin "1") (pinfunction "G_1") (pintype "passive"))
    )
    (net (code "20") (name "FRAME_VALID") (class "Default")
      (node (ref "JX1") (pin "P$71") (pinfunction "P$30_P$71") (pintype "bidirectional"))
      (node (ref "U$4") (pin "P$38") (pinfunction "FRAME_VALID_P$38") (pintype "bidirectional"))
    )
    (net (code "21") (name "GND") (class "Default")
      (node (ref "C1") (pin "2") (pinfunction "2_2") (pintype "passive"))
      (node (ref "C11") (pin "2") (pinfunction "2_2") (pintype "passive"))
      (node (ref "C12") (pin "2") (pinfunction "2_2") (pintype "passive"))
      (node (ref "C13") (pin "2") (pinfunction "2_2") (pintype "passive"))
      (node (ref "C14") (pin "2") (pinfunction "2_2") (pintype "passive"))
      (node (ref "C15") (pin "2") (pinfunction "2_2") (pintype "passive"))
      (node (ref "C16") (pin "2") (pinfunction "2_2") (pintype "passive"))
      (node (ref "C17") (pin "2") (pinfunction "2_2") (pintype "passive"))
      (node (ref "C18") (pin "2") (pinfunction "2_2") (pintype "passive"))
      (node (ref "C19") (pin "2") (pinfunction "2_2") (pintype "passive"))
      (node (ref "C2") (pin "2") (pinfunction "2_2") (pintype "passive"))
      (node (ref "C20") (pin "2") (pinfunction "2_2") (pintype "passive"))
      (node (ref "C21") (pin "2") (pinfunction "2_2") (pintype "passive"))
      (node (ref "C22") (pin "1") (pinfunction "1_1") (pintype "passive"))
      (node (ref "C23") (pin "1") (pinfunction "1_1") (pintype "passive"))
      (node (ref "C24") (pin "1") (pinfunction "1_1") (pintype "passive"))
      (node (ref "C25") (pin "1") (pinfunction "1_1") (pintype "passive"))
      (node (ref "C26") (pin "1") (pinfunction "1_1") (pintype "passive"))
      (node (ref "C27") (pin "1") (pinfunction "1_1") (pintype "passive"))
      (node (ref "C28") (pin "2") (pinfunction "2_2") (pintype "passive"))
      (node (ref "C29") (pin "2") (pinfunction "2_2") (pintype "passive"))
      (node (ref "C3") (pin "2") (pinfunction "2_2") (pintype "passive"))
      (node (ref "C30") (pin "2") (pinfunction "2_2") (pintype "passive"))
      (node (ref "C31") (pin "2") (pinfunction "2_2") (pintype "passive"))
      (node (ref "C32") (pin "2") (pinfunction "2_2") (pintype "passive"))
      (node (ref "C37") (pin "2") (pinfunction "2_2") (pintype "passive"))
      (node (ref "C38") (pin "2") (pinfunction "2_2") (pintype "passive"))
      (node (ref "C39") (pin "2") (pinfunction "2_2") (pintype "passive"))
      (node (ref "C4") (pin "2") (pinfunction "2_2") (pintype "passive"))
      (node (ref "C40") (pin "2") (pinfunction "2_2") (pintype "passive"))
      (node (ref "C41") (pin "2") (pinfunction "2_2") (pintype "passive"))
      (node (ref "C42") (pin "2") (pinfunction "2_2") (pintype "passive"))
      (node (ref "C5") (pin "2") (pinfunction "2_2") (pintype "passive"))
      (node (ref "C6") (pin "2") (pinfunction "2_2") (pintype "passive"))
      (node (ref "C7") (pin "2") (pinfunction "2_2") (pintype "passive"))
      (node (ref "HDMI_IN") (pin "11") (pinfunction "CLOCKSHIELD_11") (pintype "bidirectional"))
      (node (ref "HDMI_IN") (pin "14") (pinfunction "RES_14") (pintype "bidirectional"))
      (node (ref "HDMI_IN") (pin "17") (pinfunction "DDC/CEC-GRND_17") (pintype "bidirectional"))
      (node (ref "HDMI_IN") (pin "2") (pinfunction "DATA2SHIELD_2") (pintype "bidirectional"))
      (node (ref "HDMI_IN") (pin "5") (pinfunction "DATA1SHIELD_5") (pintype "bidirectional"))
      (node (ref "HDMI_IN") (pin "8") (pinfunction "DATA0SHIELD_8") (pintype "bidirectional"))
      (node (ref "HDMI_OUT") (pin "11") (pinfunction "CLOCKSHIELD_11") (pintype "bidirectional"))
      (node (ref "HDMI_OUT") (pin "14") (pinfunction "RES_14") (pintype "bidirectional"))
      (node (ref "HDMI_OUT") (pin "17") (pinfunction "DDC/CEC-GRND_17") (pintype "bidirectional"))
      (node (ref "HDMI_OUT") (pin "2") (pinfunction "DATA2SHIELD_2") (pintype "bidirectional"))
      (node (ref "HDMI_OUT") (pin "5") (pinfunction "DATA1SHIELD_5") (pintype "bidirectional"))
      (node (ref "HDMI_OUT") (pin "8") (pinfunction "DATA0SHIELD_8") (pintype "bidirectional"))
      (node (ref "JX1") (pin "P$1") (pinfunction "P$100_P$1") (pintype "bidirectional"))
      (node (ref "JX1") (pin "P$15") (pinfunction "P$86_P$15") (pintype "bidirectional"))
      (node (ref "JX1") (pin "P$16") (pinfunction "P$85_P$16") (pintype "bidirectional"))
      (node (ref "JX1") (pin "P$2") (pinfunction "P$99_P$2") (pintype "bidirectional"))
      (node (ref "JX1") (pin "P$24") (pinfunction "P$77_P$24") (pintype "bidirectional"))
      (node (ref "JX1") (pin "P$29") (pinfunction "P$72_P$29") (pintype "bidirectional"))
      (node (ref "JX1") (pin "P$3") (pinfunction "P$98_P$3") (pintype "bidirectional"))
      (node (ref "JX1") (pin "P$30") (pinfunction "P$71_P$30") (pintype "bidirectional"))
      (node (ref "JX1") (pin "P$35") (pinfunction "P$66_P$35") (pintype "bidirectional"))
      (node (ref "JX1") (pin "P$36") (pinfunction "P$65_P$36") (pintype "bidirectional"))
      (node (ref "JX1") (pin "P$4") (pinfunction "P$97_P$4") (pintype "bidirectional"))
      (node (ref "JX1") (pin "P$49") (pinfunction "P$52_P$49") (pintype "bidirectional"))
      (node (ref "JX1") (pin "P$5") (pinfunction "P$96_P$5") (pintype "bidirectional"))
      (node (ref "JX1") (pin "P$50") (pinfunction "P$51_P$50") (pintype "bidirectional"))
      (node (ref "JX1") (pin "P$55") (pinfunction "P$46_P$55") (pintype "bidirectional"))
      (node (ref "JX1") (pin "P$56") (pinfunction "P$45_P$56") (pintype "bidirectional"))
      (node (ref "JX1") (pin "P$6") (pinfunction "P$95_P$6") (pintype "bidirectional"))
      (node (ref "JX1") (pin "P$61") (pinfunction "P$40_P$61") (pintype "bidirectional"))
      (node (ref "JX1") (pin "P$62") (pinfunction "P$39_P$62") (pintype "bidirectional"))
      (node (ref "JX1") (pin "P$67") (pinfunction "P$34_P$67") (pintype "bidirectional"))
      (node (ref "JX1") (pin "P$68") (pinfunction "P$33_P$68") (pintype "bidirectional"))
      (node (ref "JX1") (pin "P$73") (pinfunction "P$28_P$73") (pintype "bidirectional"))
      (node (ref "JX1") (pin "P$74") (pinfunction "P$27_P$74") (pintype "bidirectional"))
      (node (ref "JX1") (pin "P$79") (pinfunction "P$22_P$79") (pintype "bidirectional"))
      (node (ref "JX1") (pin "P$80") (pinfunction "P$21_P$80") (pintype "bidirectional"))
      (node (ref "JX1") (pin "P$85") (pinfunction "P$16_P$85") (pintype "bidirectional"))
      (node (ref "JX1") (pin "P$86") (pinfunction "P$15_P$86") (pintype "bidirectional"))
      (node (ref "JX2") (pin "P$10") (pinfunction "P$91_P$10") (pintype "bidirectional"))
      (node (ref "JX2") (pin "P$15") (pinfunction "P$86_P$15") (pintype "bidirectional"))
      (node (ref "JX2") (pin "P$16") (pinfunction "P$85_P$16") (pintype "bidirectional"))
      (node (ref "JX2") (pin "P$24") (pinfunction "P$77_P$24") (pintype "bidirectional"))
      (node (ref "JX2") (pin "P$29") (pinfunction "P$72_P$29") (pintype "bidirectional"))
      (node (ref "JX2") (pin "P$30") (pinfunction "P$71_P$30") (pintype "bidirectional"))
      (node (ref "JX2") (pin "P$35") (pinfunction "P$66_P$35") (pintype "bidirectional"))
      (node (ref "JX2") (pin "P$36") (pinfunction "P$65_P$36") (pintype "bidirectional"))
      (node (ref "JX2") (pin "P$49") (pinfunction "P$52_P$49") (pintype "bidirectional"))
      (node (ref "JX2") (pin "P$50") (pinfunction "P$51_P$50") (pintype "bidirectional"))
      (node (ref "JX2") (pin "P$55") (pinfunction "P$46_P$55") (pintype "bidirectional"))
      (node (ref "JX2") (pin "P$56") (pinfunction "P$45_P$56") (pintype "bidirectional"))
      (node (ref "JX2") (pin "P$61") (pinfunction "P$40_P$61") (pintype "bidirectional"))
      (node (ref "JX2") (pin "P$62") (pinfunction "P$39_P$62") (pintype "bidirectional"))
      (node (ref "JX2") (pin "P$67") (pinfunction "P$34_P$67") (pintype "bidirectional"))
      (node (ref "JX2") (pin "P$68") (pinfunction "P$33_P$68") (pintype "bidirectional"))
      (node (ref "JX2") (pin "P$73") (pinfunction "P$28_P$73") (pintype "bidirectional"))
      (node (ref "JX2") (pin "P$74") (pinfunction "P$27_P$74") (pintype "bidirectional"))
      (node (ref "JX2") (pin "P$79") (pinfunction "P$22_P$79") (pintype "bidirectional"))
      (node (ref "JX2") (pin "P$80") (pinfunction "P$21_P$80") (pintype "bidirectional"))
      (node (ref "JX2") (pin "P$85") (pinfunction "P$16_P$85") (pintype "bidirectional"))
      (node (ref "JX2") (pin "P$86") (pinfunction "P$15_P$86") (pintype "bidirectional"))
      (node (ref "JX2") (pin "P$9") (pinfunction "P$92_P$9") (pintype "bidirectional"))
      (node (ref "K1") (pin "2") (pinfunction "2_2") (pintype "passive"))
      (node (ref "K1") (pin "3") (pinfunction "3_3") (pintype "passive"))
      (node (ref "LED1") (pin "C") (pinfunction "C_C") (pintype "passive"))
      (node (ref "LED2") (pin "C") (pinfunction "C_C") (pintype "passive"))
      (node (ref "LED3") (pin "C") (pinfunction "C_C") (pintype "passive"))
      (node (ref "LED4") (pin "C") (pinfunction "C_C") (pintype "passive"))
      (node (ref "OFF") (pin "C") (pinfunction "C_C") (pintype "passive"))
      (node (ref "ON") (pin "C") (pinfunction "C_C") (pintype "passive"))
      (node (ref "PCA9306") (pin "1") (pinfunction "GND_1") (pintype "bidirectional"))
      (node (ref "R10") (pin "2") (pinfunction "2_2") (pintype "passive"))
      (node (ref "R2") (pin "1") (pinfunction "1_1") (pintype "passive"))
      (node (ref "R21") (pin "1") (pinfunction "1_1") (pintype "passive"))
      (node (ref "R29") (pin "1") (pinfunction "1_1") (pintype "passive"))
      (node (ref "R3") (pin "1") (pinfunction "1_1") (pintype "passive"))
      (node (ref "R7") (pin "1") (pinfunction "1_1") (pintype "passive"))
      (node (ref "R8") (pin "1") (pinfunction "1_1") (pintype "passive"))
      (node (ref "U$11") (pin "9") (pinfunction "GND_9") (pintype "bidirectional"))
      (node (ref "U$14") (pin "2") (pinfunction "GND_2") (pintype "bidirectional"))
      (node (ref "U$15") (pin "2") (pinfunction "GND_2") (pintype "bidirectional"))
      (node (ref "U$17") (pin "2") (pinfunction "S_2") (pintype "passive"))
      (node (ref "U$18") (pin "P$3") (pinfunction "GND_P$3") (pintype "bidirectional"))
      (node (ref "U$2") (pin "2") (pinfunction "S_2") (pintype "passive"))
      (node (ref "U$4") (pin "P$1") (pinfunction "GNDO_P$1") (pintype "bidirectional"))
      (node (ref "U$4") (pin "P$20") (pinfunction "GNDA2_P$20") (pintype "bidirectional"))
      (node (ref "U$4") (pin "P$22") (pinfunction "GNDADC1_P$22") (pintype "bidirectional"))
      (node (ref "U$4") (pin "P$24") (pinfunction "GNDD1_P$24") (pintype "bidirectional"))
      (node (ref "U$4") (pin "P$3") (pinfunction "GNDA_P$3") (pintype "bidirectional"))
      (node (ref "U$4") (pin "P$31") (pinfunction "GNDADC_P$31") (pintype "bidirectional"))
      (node (ref "U$4") (pin "P$41") (pinfunction "VRESET_3_P$41") (pintype "bidirectional"))
      (node (ref "U$4") (pin "P$42") (pinfunction "VRESET_2_P$42") (pintype "bidirectional"))
      (node (ref "U$4") (pin "P$44") (pinfunction "GND_DRIVERS_P$44") (pintype "bidirectional"))
      (node (ref "U$4") (pin "P$7") (pinfunction "GNDA1_P$7") (pintype "bidirectional"))
      (node (ref "U$4") (pin "P$9") (pinfunction "GNDD_P$9") (pintype "bidirectional"))
      (node (ref "U$5") (pin "9") (pinfunction "GND_9") (pintype "bidirectional"))
      (node (ref "U$6") (pin "2") (pinfunction "GND_2") (pintype "bidirectional"))
      (node (ref "U$7") (pin "2") (pinfunction "S_2") (pintype "passive"))
    )
    (net (code "22") (name "HDMI_OSC") (class "Default")
      (node (ref "JX2") (pin "P$47") (pinfunction "P$54_P$47") (pintype "bidirectional"))
      (node (ref "U$18") (pin "P$4") (pinfunction "CLK_P$4") (pintype "bidirectional"))
    )
    (net (code "23") (name "HDMI_PU") (class "Default")
      (node (ref "R22") (pin "1") (pinfunction "1_1") (pintype "passive"))
      (node (ref "RN3") (pin "3") (pinfunction "2_3") (pintype "passive"))
      (node (ref "RN3") (pin "4") (pinfunction "2_4") (pintype "passive"))
      (node (ref "RN4") (pin "3") (pinfunction "2_3") (pintype "passive"))
      (node (ref "RN4") (pin "4") (pinfunction "2_4") (pintype "passive"))
      (node (ref "RN5") (pin "3") (pinfunction "2_3") (pintype "passive"))
      (node (ref "RN5") (pin "4") (pinfunction "2_4") (pintype "passive"))
      (node (ref "RN6") (pin "3") (pinfunction "2_3") (pintype "passive"))
      (node (ref "RN6") (pin "4") (pinfunction "2_4") (pintype "passive"))
    )
    (net (code "24") (name "INT_TIME1") (class "Default")
      (node (ref "JX1") (pin "P$65") (pinfunction "P$36_P$65") (pintype "bidirectional"))
      (node (ref "U$4") (pin "P$11") (pinfunction "INT_TIME_1_P$11") (pintype "bidirectional"))
    )
    (net (code "25") (name "INT_TIME2") (class "Default")
      (node (ref "JX1") (pin "P$63") (pinfunction "P$38_P$63") (pintype "bidirectional"))
      (node (ref "U$4") (pin "P$12") (pinfunction "INT_TIME_2_P$12") (pintype "bidirectional"))
    )
    (net (code "26") (name "INT_TIME3") (class "Default")
      (node (ref "JX1") (pin "P$69") (pinfunction "P$32_P$69") (pintype "bidirectional"))
      (node (ref "U$4") (pin "P$37") (pinfunction "INT_TIME_3_P$37") (pintype "bidirectional"))
    )
    (net (code "27") (name "LED1") (class "Default")
      (node (ref "JX2") (pin "P$19") (pinfunction "P$82_P$19") (pintype "bidirectional"))
      (node (ref "R20") (pin "2") (pinfunction "2_2") (pintype "passive"))
    )
    (net (code "28") (name "LED2") (class "Default")
      (node (ref "JX2") (pin "P$17") (pinfunction "P$84_P$17") (pintype "bidirectional"))
      (node (ref "R19") (pin "2") (pinfunction "2_2") (pintype "passive"))
    )
    (net (code "29") (name "LED3") (class "Default")
      (node (ref "JX2") (pin "P$13") (pinfunction "P$88_P$13") (pintype "bidirectional"))
      (node (ref "R6") (pin "2") (pinfunction "2_2") (pintype "passive"))
    )
    (net (code "30") (name "LED4") (class "Default")
      (node (ref "JX2") (pin "P$11") (pinfunction "P$90_P$11") (pintype "bidirectional"))
      (node (ref "R5") (pin "2") (pinfunction "2_2") (pintype "passive"))
    )
    (net (code "31") (name "LINE_VALID") (class "Default")
      (node (ref "JX1") (pin "P$75") (pinfunction "P$26_P$75") (pintype "bidirectional"))
      (node (ref "U$4") (pin "P$39") (pinfunction "LINE_VALID_P$39") (pintype "bidirectional"))
    )
    (net (code "32") (name "LPOWEN") (class "Default")
      (node (ref "JX1") (pin "P$90") (pinfunction "P$11_P$90") (pintype "bidirectional"))
      (node (ref "U$14") (pin "3") (pinfunction "EN_3") (pintype "bidirectional"))
      (node (ref "U$15") (pin "3") (pinfunction "EN_3") (pintype "bidirectional"))
      (node (ref "U$5") (pin "4") (pinfunction "EN_4") (pintype "bidirectional"))
      (node (ref "U$6") (pin "3") (pinfunction "EN_3") (pintype "bidirectional"))
    )
    (net (code "33") (name "Net-(C21-Pad1)") (class "Default")
      (node (ref "C21") (pin "1") (pinfunction "1_1") (pintype "passive"))
      (node (ref "HDMI_IN") (pin "SH1") (pinfunction "SH1_SH1") (pintype "bidirectional"))
      (node (ref "HDMI_IN") (pin "SH2") (pinfunction "SH2_SH2") (pintype "bidirectional"))
      (node (ref "HDMI_IN") (pin "SH3") (pinfunction "SH3_SH3") (pintype "bidirectional"))
      (node (ref "HDMI_IN") (pin "SH4") (pinfunction "SH4_SH4") (pintype "bidirectional"))
      (node (ref "R8") (pin "2") (pinfunction "2_2") (pintype "passive"))
    )
    (net (code "34") (name "Net-(C28-Pad1)") (class "Default")
      (node (ref "C28") (pin "1") (pinfunction "1_1") (pintype "passive"))
      (node (ref "HDMI_OUT") (pin "SH1") (pinfunction "SH1_SH1") (pintype "bidirectional"))
      (node (ref "HDMI_OUT") (pin "SH2") (pinfunction "SH2_SH2") (pintype "bidirectional"))
      (node (ref "HDMI_OUT") (pin "SH3") (pinfunction "SH3_SH3") (pintype "bidirectional"))
      (node (ref "HDMI_OUT") (pin "SH4") (pinfunction "SH4_SH4") (pintype "bidirectional"))
      (node (ref "R21") (pin "2") (pinfunction "2_2") (pintype "passive"))
    )
    (net (code "35") (name "Net-(HDMI_IN-DETECT)") (class "Default")
      (node (ref "HDMI_IN") (pin "19") (pinfunction "DETECT_19") (pintype "bidirectional"))
      (node (ref "R30") (pin "1") (pinfunction "1_1") (pintype "passive"))
      (node (ref "U$17") (pin "3") (pinfunction "D_3") (pintype "passive"))
    )
    (net (code "36") (name "Net-(HDMI_IN-SCL)") (class "Default")
      (node (ref "HDMI_IN") (pin "15") (pinfunction "SCL_15") (pintype "bidirectional"))
      (node (ref "PCA9306") (pin "6") (pinfunction "SCL2_6") (pintype "bidirectional"))
      (node (ref "RN7") (pin "6") (pinfunction "2_6") (pintype "passive"))
    )
    (net (code "37") (name "Net-(HDMI_IN-SDA)") (class "Default")
      (node (ref "HDMI_IN") (pin "16") (pinfunction "SDA_16") (pintype "bidirectional"))
      (node (ref "PCA9306") (pin "5") (pinfunction "SDA2_5") (pintype "bidirectional"))
      (node (ref "RN7") (pin "5") (pinfunction "2_5") (pintype "passive"))
    )
    (net (code "38") (name "Net-(HDMI_OUT-+5V)") (class "Default")
      (node (ref "HDMI_OUT") (pin "18") (pinfunction "+5V_18") (pintype "bidirectional"))
      (node (ref "R32") (pin "2") (pinfunction "2_2") (pintype "passive"))
    )
    (net (code "39") (name "Net-(HDMI_OUT-DETECT)") (class "Default")
      (node (ref "HDMI_OUT") (pin "19") (pinfunction "DETECT_19") (pintype "bidirectional"))
      (node (ref "R29") (pin "2") (pinfunction "2_2") (pintype "passive"))
    )
    (net (code "40") (name "Net-(LED1-PadA)") (class "Default")
      (node (ref "LED1") (pin "A") (pinfunction "A_A") (pintype "passive"))
      (node (ref "R5") (pin "1") (pinfunction "1_1") (pintype "passive"))
    )
    (net (code "41") (name "Net-(LED2-PadA)") (class "Default")
      (node (ref "LED2") (pin "A") (pinfunction "A_A") (pintype "passive"))
      (node (ref "R6") (pin "1") (pinfunction "1_1") (pintype "passive"))
    )
    (net (code "42") (name "Net-(LED3-PadA)") (class "Default")
      (node (ref "LED3") (pin "A") (pinfunction "A_A") (pintype "passive"))
      (node (ref "R19") (pin "1") (pinfunction "1_1") (pintype "passive"))
    )
    (net (code "43") (name "Net-(LED4-PadA)") (class "Default")
      (node (ref "LED4") (pin "A") (pinfunction "A_A") (pintype "passive"))
      (node (ref "R20") (pin "1") (pinfunction "1_1") (pintype "passive"))
    )
    (net (code "44") (name "Net-(OFF-PadA)") (class "Default")
      (node (ref "OFF") (pin "A") (pinfunction "A_A") (pintype "passive"))
      (node (ref "R12") (pin "1") (pinfunction "1_1") (pintype "passive"))
    )
    (net (code "45") (name "Net-(ON-PadA)") (class "Default")
      (node (ref "ON") (pin "A") (pinfunction "A_A") (pintype "passive"))
      (node (ref "R11") (pin "2") (pinfunction "2_2") (pintype "passive"))
    )
    (net (code "46") (name "Net-(U$1-1)") (class "Default")
      (node (ref "L1") (pin "1") (pinfunction "1_1") (pintype "passive"))
      (node (ref "R11") (pin "1") (pinfunction "1_1") (pintype "passive"))
      (node (ref "U$1") (pin "P$3") (pinfunction "1_P$3") (pintype "bidirectional"))
    )
    (net (code "47") (name "Net-(U$2-G)") (class "Default")
      (node (ref "C3") (pin "1") (pinfunction "1_1") (pintype "passive"))
      (node (ref "R1") (pin "1") (pinfunction "1_1") (pintype "passive"))
      (node (ref "R2") (pin "2") (pinfunction "2_2") (pintype "passive"))
      (node (ref "U$2") (pin "1") (pinfunction "G_1") (pintype "passive"))
    )
    (net (code "48") (name "Net-(U$3-A)") (class "Default")
      (node (ref "R4") (pin "1") (pinfunction "1_1") (pintype "passive"))
      (node (ref "U$3") (pin "1") (pinfunction "A_1") (pintype "passive"))
    )
    (net (code "49") (name "Net-(U$5-BYP)") (class "Default")
      (node (ref "C7") (pin "1") (pinfunction "1_1") (pintype "passive"))
      (node (ref "U$5") (pin "3") (pinfunction "BYP_3") (pintype "bidirectional"))
    )
    (net (code "50") (name "Net-(U$5-REF)") (class "Default")
      (node (ref "C31") (pin "1") (pinfunction "1_1") (pintype "passive"))
      (node (ref "U$5") (pin "5") (pinfunction "REF_SEN_5") (pintype "bidirectional"))
      (node (ref "U$5") (pin "6") (pinfunction "REF_6") (pintype "bidirectional"))
    )
    (net (code "51") (name "Net-(U$5-VOUT)") (class "Default")
      (node (ref "C6") (pin "1") (pinfunction "1_1") (pintype "passive"))
      (node (ref "F1") (pin "2") (pinfunction "2_2") (pintype "passive"))
      (node (ref "F2") (pin "2") (pinfunction "2_2") (pintype "passive"))
      (node (ref "F3") (pin "2") (pinfunction "2_2") (pintype "passive"))
      (node (ref "U$5") (pin "1") (pinfunction "VOUT_1") (pintype "bidirectional"))
      (node (ref "U$5") (pin "2") (pinfunction "VO_SEN_2") (pintype "bidirectional"))
    )
    (net (code "52") (name "Net-(U$5-VREG)") (class "Default")
      (node (ref "C30") (pin "1") (pinfunction "1_1") (pintype "passive"))
      (node (ref "U$5") (pin "7") (pinfunction "VREG_7") (pintype "bidirectional"))
    )
    (net (code "53") (name "Net-(U$8-A)") (class "Default")
      (node (ref "R9") (pin "1") (pinfunction "1_1") (pintype "passive"))
      (node (ref "U$8") (pin "1") (pinfunction "A_1") (pintype "passive"))
    )
    (net (code "54") (name "Net-(U$11-BYP)") (class "Default")
      (node (ref "C18") (pin "1") (pinfunction "1_1") (pintype "passive"))
      (node (ref "U$11") (pin "3") (pinfunction "BYP_3") (pintype "bidirectional"))
    )
    (net (code "55") (name "Net-(U$11-REF)") (class "Default")
      (node (ref "C17") (pin "1") (pinfunction "1_1") (pintype "passive"))
      (node (ref "U$11") (pin "5") (pinfunction "REF_SEN_5") (pintype "bidirectional"))
      (node (ref "U$11") (pin "6") (pinfunction "REF_6") (pintype "bidirectional"))
    )
    (net (code "56") (name "Net-(U$11-VREG)") (class "Default")
      (node (ref "C16") (pin "1") (pinfunction "1_1") (pintype "passive"))
      (node (ref "U$11") (pin "7") (pinfunction "VREG_7") (pintype "bidirectional"))
    )
    (net (code "57") (name "P1_CLOCK+") (class "Default")
      (node (ref "HDMI_IN") (pin "10") (pinfunction "CLOCK+_10") (pintype "bidirectional"))
      (node (ref "JX2") (pin "P$48") (pinfunction "P$53_P$48") (pintype "bidirectional"))
      (node (ref "RN3") (pin "2") (pinfunction "1_2") (pintype "passive"))
    )
    (net (code "58") (name "P1_CLOCK-") (class "Default")
      (node (ref "HDMI_IN") (pin "12") (pinfunction "CLOCK-_12") (pintype "bidirectional"))
      (node (ref "JX2") (pin "P$46") (pinfunction "P$55_P$46") (pintype "bidirectional"))
      (node (ref "RN3") (pin "1") (pinfunction "1_1") (pintype "passive"))
    )
    (net (code "59") (name "P1_DATA0+") (class "Default")
      (node (ref "HDMI_IN") (pin "7") (pinfunction "DATA0+_7") (pintype "bidirectional"))
      (node (ref "JX2") (pin "P$40") (pinfunction "P$61_P$40") (pintype "bidirectional"))
      (node (ref "RN4") (pin "2") (pinfunction "1_2") (pintype "passive"))
    )
    (net (code "60") (name "P1_DATA0-") (class "Default")
      (node (ref "HDMI_IN") (pin "9") (pinfunction "DATA0-_9") (pintype "bidirectional"))
      (node (ref "JX2") (pin "P$38") (pinfunction "P$63_P$38") (pintype "bidirectional"))
      (node (ref "RN4") (pin "1") (pinfunction "1_1") (pintype "passive"))
    )
    (net (code "61") (name "P1_DATA1+") (class "Default")
      (node (ref "HDMI_IN") (pin "4") (pinfunction "DATA1+_4") (pintype "bidirectional"))
      (node (ref "JX2") (pin "P$34") (pinfunction "P$67_P$34") (pintype "bidirectional"))
      (node (ref "RN5") (pin "2") (pinfunction "1_2") (pintype "passive"))
    )
    (net (code "62") (name "P1_DATA1-") (class "Default")
      (node (ref "HDMI_IN") (pin "6") (pinfunction "DATA1-_6") (pintype "bidirectional"))
      (node (ref "JX2") (pin "P$32") (pinfunction "P$69_P$32") (pintype "bidirectional"))
      (node (ref "RN5") (pin "1") (pinfunction "1_1") (pintype "passive"))
    )
    (net (code "63") (name "P1_DATA2+") (class "Default")
      (node (ref "HDMI_IN") (pin "1") (pinfunction "DATA2+_1") (pintype "bidirectional"))
      (node (ref "JX2") (pin "P$28") (pinfunction "P$73_P$28") (pintype "bidirectional"))
      (node (ref "RN6") (pin "2") (pinfunction "1_2") (pintype "passive"))
    )
    (net (code "64") (name "P1_DATA2-") (class "Default")
      (node (ref "HDMI_IN") (pin "3") (pinfunction "DATA2-_3") (pintype "bidirectional"))
      (node (ref "JX2") (pin "P$26") (pinfunction "P$75_P$26") (pintype "bidirectional"))
      (node (ref "RN6") (pin "1") (pinfunction "1_1") (pintype "passive"))
    )
    (net (code "65") (name "P2_CLOCK+") (class "Default")
      (node (ref "HDMI_OUT") (pin "10") (pinfunction "CLOCK+_10") (pintype "bidirectional"))
      (node (ref "JX1") (pin "P$53") (pinfunction "P$48_P$53") (pintype "bidirectional"))
    )
    (net (code "66") (name "P2_CLOCK-") (class "Default")
      (node (ref "HDMI_OUT") (pin "12") (pinfunction "CLOCK-_12") (pintype "bidirectional"))
      (node (ref "JX1") (pin "P$51") (pinfunction "P$50_P$51") (pintype "bidirectional"))
    )
    (net (code "67") (name "P2_DATA0+") (class "Default")
      (node (ref "HDMI_OUT") (pin "7") (pinfunction "DATA0+_7") (pintype "bidirectional"))
      (node (ref "JX1") (pin "P$47") (pinfunction "P$54_P$47") (pintype "bidirectional"))
    )
    (net (code "68") (name "P2_DATA0-") (class "Default")
      (node (ref "HDMI_OUT") (pin "9") (pinfunction "DATA0-_9") (pintype "bidirectional"))
      (node (ref "JX1") (pin "P$45") (pinfunction "P$56_P$45") (pintype "bidirectional"))
    )
    (net (code "69") (name "P2_DATA1+") (class "Default")
      (node (ref "HDMI_OUT") (pin "4") (pinfunction "DATA1+_4") (pintype "bidirectional"))
      (node (ref "JX1") (pin "P$39") (pinfunction "P$62_P$39") (pintype "bidirectional"))
    )
    (net (code "70") (name "P2_DATA1-") (class "Default")
      (node (ref "HDMI_OUT") (pin "6") (pinfunction "DATA1-_6") (pintype "bidirectional"))
      (node (ref "JX1") (pin "P$37") (pinfunction "P$64_P$37") (pintype "bidirectional"))
    )
    (net (code "71") (name "P2_DATA2+") (class "Default")
      (node (ref "HDMI_OUT") (pin "1") (pinfunction "DATA2+_1") (pintype "bidirectional"))
      (node (ref "JX1") (pin "P$33") (pinfunction "P$68_P$33") (pintype "bidirectional"))
    )
    (net (code "72") (name "P2_DATA2-") (class "Default")
      (node (ref "HDMI_OUT") (pin "3") (pinfunction "DATA2-_3") (pintype "bidirectional"))
      (node (ref "JX1") (pin "P$31") (pinfunction "P$70_P$31") (pintype "bidirectional"))
    )
    (net (code "73") (name "PG_CARRIER") (class "Default")
      (node (ref "JX2") (pin "P$90") (pinfunction "P$11_P$90") (pintype "bidirectional"))
    )
    (net (code "74") (name "PRECHARGE_BIAS") (class "Default")
      (node (ref "C22") (pin "2") (pinfunction "2_2") (pintype "passive"))
      (node (ref "R23") (pin "1") (pinfunction "1_1") (pintype "passive"))
      (node (ref "U$4") (pin "P$40") (pinfunction "PRECHARGE_BIAS_P$40") (pintype "bidirectional"))
    )
    (net (code "75") (name "PWR_EN") (class "Default")
      (node (ref "JX1") (pin "P$96") (pinfunction "P$5_P$96") (pintype "bidirectional"))
      (node (ref "R3") (pin "2") (pinfunction "2_2") (pintype "passive"))
      (node (ref "U$2") (pin "3") (pinfunction "D_3") (pintype "passive"))
      (node (ref "U$3") (pin "3") (pinfunction "C_3") (pintype "passive"))
    )
    (net (code "76") (name "RESET") (class "Default")
      (node (ref "JX1") (pin "P$77") (pinfunction "P$24_P$77") (pintype "bidirectional"))
      (node (ref "U$4") (pin "P$6") (pinfunction "RESET_N_P$6") (pintype "bidirectional"))
    )
    (net (code "77") (name "SCL2") (class "Default")
      (node (ref "JX2") (pin "P$12") (pinfunction "P$89_P$12") (pintype "bidirectional"))
      (node (ref "PCA9306") (pin "3") (pinfunction "SCL1_3") (pintype "bidirectional"))
      (node (ref "RN7") (pin "8") (pinfunction "2_8") (pintype "passive"))
    )
    (net (code "78") (name "SCLC") (class "Default")
      (node (ref "JX1") (pin "P$82") (pinfunction "P$19_P$82") (pintype "bidirectional"))
      (node (ref "U$18") (pin "P$2") (pinfunction "SCL_P$2") (pintype "bidirectional"))
    )
    (net (code "79") (name "SDA2") (class "Default")
      (node (ref "JX2") (pin "P$14") (pinfunction "P$87_P$14") (pintype "bidirectional"))
      (node (ref "PCA9306") (pin "4") (pinfunction "SDA1_4") (pintype "bidirectional"))
      (node (ref "RN7") (pin "7") (pinfunction "2_7") (pintype "passive"))
    )
    (net (code "80") (name "SDAC") (class "Default")
      (node (ref "JX1") (pin "P$84") (pinfunction "P$17_P$84") (pintype "bidirectional"))
      (node (ref "U$18") (pin "P$1") (pinfunction "SDA_P$1") (pintype "bidirectional"))
    )
    (net (code "81") (name "SPI_CLK") (class "Default")
      (node (ref "JX1") (pin "P$87") (pinfunction "P$14_P$87") (pintype "bidirectional"))
      (node (ref "U$4") (pin "P$47") (pinfunction "SPI_CLK_P$47") (pintype "bidirectional"))
    )
    (net (code "82") (name "SPI_DATA") (class "Default")
      (node (ref "JX1") (pin "P$83") (pinfunction "P$18_P$83") (pintype "bidirectional"))
      (node (ref "U$4") (pin "P$46") (pinfunction "SPI_DATA_P$46") (pintype "bidirectional"))
    )
    (net (code "83") (name "SPI_EN") (class "Default")
      (node (ref "JX1") (pin "P$89") (pinfunction "P$12_P$89") (pintype "bidirectional"))
      (node (ref "U$4") (pin "P$48") (pinfunction "SPI_EN_P$48") (pintype "bidirectional"))
    )
    (net (code "84") (name "VADC") (class "Default")
      (node (ref "C4") (pin "1") (pinfunction "1_1") (pintype "passive"))
      (node (ref "F3") (pin "1") (pinfunction "1_1") (pintype "passive"))
      (node (ref "R24") (pin "2") (pinfunction "2_2") (pintype "passive"))
      (node (ref "U$4") (pin "P$21") (pinfunction "VADC2_P$21") (pintype "bidirectional"))
      (node (ref "U$4") (pin "P$30") (pinfunction "VADC_P$30") (pintype "bidirectional"))
      (node (ref "U$4") (pin "P$4") (pinfunction "VADC1_P$4") (pintype "bidirectional"))
    )
    (net (code "85") (name "VCCIO") (class "Default")
      (node (ref "C14") (pin "1") (pinfunction "1_1") (pintype "passive"))
      (node (ref "C15") (pin "1") (pinfunction "1_1") (pintype "passive"))
      (node (ref "C19") (pin "1") (pinfunction "1_1") (pintype "passive"))
      (node (ref "C32") (pin "1") (pinfunction "1_1") (pintype "passive"))
      (node (ref "JX1") (pin "P$21") (pinfunction "P$80_P$21") (pintype "bidirectional"))
      (node (ref "JX1") (pin "P$22") (pinfunction "P$79_P$22") (pintype "bidirectional"))
      (node (ref "JX1") (pin "P$23") (pinfunction "P$78_P$23") (pintype "bidirectional"))
      (node (ref "JX2") (pin "P$21") (pinfunction "P$80_P$21") (pintype "bidirectional"))
      (node (ref "JX2") (pin "P$22") (pinfunction "P$79_P$22") (pintype "bidirectional"))
      (node (ref "JX2") (pin "P$23") (pinfunction "P$78_P$23") (pintype "bidirectional"))
      (node (ref "PCA9306") (pin "2") (pinfunction "VREF1_2") (pintype "bidirectional"))
      (node (ref "R22") (pin "2") (pinfunction "2_2") (pintype "passive"))
      (node (ref "R31") (pin "1") (pinfunction "1_1") (pintype "passive"))
      (node (ref "RN7") (pin "1") (pinfunction "1_1") (pintype "passive"))
      (node (ref "RN7") (pin "2") (pinfunction "1_2") (pintype "passive"))
      (node (ref "U$11") (pin "1") (pinfunction "VOUT_1") (pintype "bidirectional"))
      (node (ref "U$11") (pin "2") (pinfunction "VO_SEN_2") (pintype "bidirectional"))
      (node (ref "U$18") (pin "P$6") (pinfunction "VDD_P$6") (pintype "bidirectional"))
      (node (ref "U$4") (pin "P$43") (pinfunction "VRESET_1_P$43") (pintype "bidirectional"))
      (node (ref "U$4") (pin "P$45") (pinfunction "VMEM_H_P$45") (pintype "bidirectional"))
    )
    (net (code "86") (name "VCCIO_EN") (class "Default")
      (node (ref "JX2") (pin "P$91") (pinfunction "P$10_P$91") (pintype "bidirectional"))
      (node (ref "R10") (pin "1") (pinfunction "1_1") (pintype "passive"))
      (node (ref "U$11") (pin "4") (pinfunction "EN_4") (pintype "bidirectional"))
      (node (ref "U$7") (pin "3") (pinfunction "D_3") (pintype "passive"))
      (node (ref "U$8") (pin "3") (pinfunction "C_3") (pintype "passive"))
    )
    (net (code "87") (name "VDDA") (class "Default")
      (node (ref "C5") (pin "1") (pinfunction "1_1") (pintype "passive"))
      (node (ref "F2") (pin "1") (pinfunction "1_1") (pintype "passive"))
      (node (ref "R25") (pin "2") (pinfunction "2_2") (pintype "passive"))
      (node (ref "R26") (pin "2") (pinfunction "2_2") (pintype "passive"))
      (node (ref "R27") (pin "2") (pinfunction "2_2") (pintype "passive"))
      (node (ref "R28") (pin "2") (pinfunction "2_2") (pintype "passive"))
      (node (ref "U$4") (pin "P$19") (pinfunction "VDDA1_P$19") (pintype "bidirectional"))
      (node (ref "U$4") (pin "P$8") (pinfunction "VDDA_P$8") (pintype "bidirectional"))
    )
    (net (code "88") (name "VDDD") (class "Default")
      (node (ref "C38") (pin "1") (pinfunction "1_1") (pintype "passive"))
      (node (ref "U$4") (pin "P$10") (pinfunction "VDDD_P$10") (pintype "bidirectional"))
      (node (ref "U$6") (pin "5") (pinfunction "VOUT_5") (pintype "bidirectional"))
    )
    (net (code "89") (name "VDDD1") (class "Default")
      (node (ref "C42") (pin "1") (pinfunction "1_1") (pintype "passive"))
      (node (ref "U$15") (pin "5") (pinfunction "VOUT_5") (pintype "bidirectional"))
      (node (ref "U$4") (pin "P$23") (pinfunction "VDDD1_P$23") (pintype "bidirectional"))
    )
    (net (code "90") (name "VDDO") (class "Default")
      (node (ref "C40") (pin "1") (pinfunction "1_1") (pintype "passive"))
      (node (ref "U$14") (pin "5") (pinfunction "VOUT_5") (pintype "bidirectional"))
      (node (ref "U$4") (pin "P$2") (pinfunction "VDDO_P$2") (pintype "bidirectional"))
    )
    (net (code "91") (name "VIN") (class "Default")
      (node (ref "K1") (pin "1") (pinfunction "1_1") (pintype "passive"))
      (node (ref "U$1") (pin "P$4") (pinfunction "2_P$4") (pintype "bidirectional"))
    )
    (net (code "92") (name "VPIX") (class "Default")
      (node (ref "C20") (pin "1") (pinfunction "1_1") (pintype "passive"))
      (node (ref "F1") (pin "1") (pinfunction "1_1") (pintype "passive"))
      (node (ref "R23") (pin "2") (pinfunction "2_2") (pintype "passive"))
      (node (ref "U$4") (pin "P$13") (pinfunction "VPIX_P$13") (pintype "bidirectional"))
    )
    (net (code "93") (name "unconnected-(HDMI_IN-CEC-Pad13)") (class "Default")
      (node (ref "HDMI_IN") (pin "13") (pinfunction "CEC_13") (pintype "bidirectional"))
    )
    (net (code "94") (name "unconnected-(HDMI_OUT-CEC-Pad13)") (class "Default")
      (node (ref "HDMI_OUT") (pin "13") (pinfunction "CEC_13") (pintype "bidirectional"))
    )
    (net (code "95") (name "unconnected-(HDMI_OUT-SCL-Pad15)") (class "Default")
      (node (ref "HDMI_OUT") (pin "15") (pinfunction "SCL_15") (pintype "bidirectional"))
    )
    (net (code "96") (name "unconnected-(HDMI_OUT-SDA-Pad16)") (class "Default")
      (node (ref "HDMI_OUT") (pin "16") (pinfunction "SDA_16") (pintype "bidirectional"))
    )
    (net (code "97") (name "unconnected-(JX1-P$1-PadP$100)") (class "Default")
      (node (ref "JX1") (pin "P$100") (pinfunction "P$1_P$100") (pintype "bidirectional"))
    )
    (net (code "98") (name "unconnected-(JX1-P$2-PadP$99)") (class "Default")
      (node (ref "JX1") (pin "P$99") (pinfunction "P$2_P$99") (pintype "bidirectional"))
    )
    (net (code "99") (name "unconnected-(JX1-P$3-PadP$98)") (class "Default")
      (node (ref "JX1") (pin "P$98") (pinfunction "P$3_P$98") (pintype "bidirectional"))
    )
    (net (code "100") (name "unconnected-(JX1-P$4-PadP$97)") (class "Default")
      (node (ref "JX1") (pin "P$97") (pinfunction "P$4_P$97") (pintype "bidirectional"))
    )
    (net (code "101") (name "unconnected-(JX1-P$6-PadP$95)") (class "Default")
      (node (ref "JX1") (pin "P$95") (pinfunction "P$6_P$95") (pintype "bidirectional"))
    )
    (net (code "102") (name "unconnected-(JX1-P$7-PadP$94)") (class "Default")
      (node (ref "JX1") (pin "P$94") (pinfunction "P$7_P$94") (pintype "bidirectional"))
    )
    (net (code "103") (name "unconnected-(JX1-P$8-PadP$93)") (class "Default")
      (node (ref "JX1") (pin "P$93") (pinfunction "P$8_P$93") (pintype "bidirectional"))
    )
    (net (code "104") (name "unconnected-(JX1-P$9-PadP$92)") (class "Default")
      (node (ref "JX1") (pin "P$92") (pinfunction "P$9_P$92") (pintype "bidirectional"))
    )
    (net (code "105") (name "unconnected-(JX1-P$10-PadP$91)") (class "Default")
      (node (ref "JX1") (pin "P$91") (pinfunction "P$10_P$91") (pintype "bidirectional"))
    )
    (net (code "106") (name "unconnected-(JX1-P$13-PadP$88)") (class "Default")
      (node (ref "JX1") (pin "P$88") (pinfunction "P$13_P$88") (pintype "bidirectional"))
    )
    (net (code "107") (name "unconnected-(JX1-P$20-PadP$81)") (class "Default")
      (node (ref "JX1") (pin "P$81") (pinfunction "P$20_P$81") (pintype "bidirectional"))
    )
    (net (code "108") (name "unconnected-(JX1-P$23-PadP$78)") (class "Default")
      (node (ref "JX1") (pin "P$78") (pinfunction "P$23_P$78") (pintype "bidirectional"))
    )
    (net (code "109") (name "unconnected-(JX1-P$25-PadP$76)") (class "Default")
      (node (ref "JX1") (pin "P$76") (pinfunction "P$25_P$76") (pintype "bidirectional"))
    )
    (net (code "110") (name "unconnected-(JX1-P$29-PadP$72)") (class "Default")
      (node (ref "JX1") (pin "P$72") (pinfunction "P$29_P$72") (pintype "bidirectional"))
    )
    (net (code "111") (name "unconnected-(JX1-P$31-PadP$70)") (class "Default")
      (node (ref "JX1") (pin "P$70") (pinfunction "P$31_P$70") (pintype "bidirectional"))
    )
    (net (code "112") (name "unconnected-(JX1-P$35-PadP$66)") (class "Default")
      (node (ref "JX1") (pin "P$66") (pinfunction "P$35_P$66") (pintype "bidirectional"))
    )
    (net (code "113") (name "unconnected-(JX1-P$37-PadP$64)") (class "Default")
      (node (ref "JX1") (pin "P$64") (pinfunction "P$37_P$64") (pintype "bidirectional"))
    )
    (net (code "114") (name "unconnected-(JX1-P$41-PadP$60)") (class "Default")
      (node (ref "JX1") (pin "P$60") (pinfunction "P$41_P$60") (pintype "bidirectional"))
    )
    (net (code "115") (name "unconnected-(JX1-P$43-PadP$58)") (class "Default")
      (node (ref "JX1") (pin "P$58") (pinfunction "P$43_P$58") (pintype "bidirectional"))
    )
    (net (code "116") (name "unconnected-(JX1-P$44-PadP$57)") (class "Default")
      (node (ref "JX1") (pin "P$57") (pinfunction "P$44_P$57") (pintype "bidirectional"))
    )
    (net (code "117") (name "unconnected-(JX1-P$47-PadP$54)") (class "Default")
      (node (ref "JX1") (pin "P$54") (pinfunction "P$47_P$54") (pintype "bidirectional"))
    )
    (net (code "118") (name "unconnected-(JX1-P$49-PadP$52)") (class "Default")
      (node (ref "JX1") (pin "P$52") (pinfunction "P$49_P$52") (pintype "bidirectional"))
    )
    (net (code "119") (name "unconnected-(JX1-P$53-PadP$48)") (class "Default")
      (node (ref "JX1") (pin "P$48") (pinfunction "P$53_P$48") (pintype "bidirectional"))
    )
    (net (code "120") (name "unconnected-(JX1-P$55-PadP$46)") (class "Default")
      (node (ref "JX1") (pin "P$46") (pinfunction "P$55_P$46") (pintype "bidirectional"))
    )
    (net (code "121") (name "unconnected-(JX1-P$61-PadP$40)") (class "Default")
      (node (ref "JX1") (pin "P$40") (pinfunction "P$61_P$40") (pintype "bidirectional"))
    )
    (net (code "122") (name "unconnected-(JX1-P$63-PadP$38)") (class "Default")
      (node (ref "JX1") (pin "P$38") (pinfunction "P$63_P$38") (pintype "bidirectional"))
    )
    (net (code "123") (name "unconnected-(JX1-P$67-PadP$34)") (class "Default")
      (node (ref "JX1") (pin "P$34") (pinfunction "P$67_P$34") (pintype "bidirectional"))
    )
    (net (code "124") (name "unconnected-(JX1-P$69-PadP$32)") (class "Default")
      (node (ref "JX1") (pin "P$32") (pinfunction "P$69_P$32") (pintype "bidirectional"))
    )
    (net (code "125") (name "unconnected-(JX1-P$73-PadP$28)") (class "Default")
      (node (ref "JX1") (pin "P$28") (pinfunction "P$73_P$28") (pintype "bidirectional"))
    )
    (net (code "126") (name "unconnected-(JX1-P$74-PadP$27)") (class "Default")
      (node (ref "JX1") (pin "P$27") (pinfunction "P$74_P$27") (pintype "bidirectional"))
    )
    (net (code "127") (name "unconnected-(JX1-P$75-PadP$26)") (class "Default")
      (node (ref "JX1") (pin "P$26") (pinfunction "P$75_P$26") (pintype "bidirectional"))
    )
    (net (code "128") (name "unconnected-(JX1-P$76-PadP$25)") (class "Default")
      (node (ref "JX1") (pin "P$25") (pinfunction "P$76_P$25") (pintype "bidirectional"))
    )
    (net (code "129") (name "unconnected-(JX1-P$81-PadP$20)") (class "Default")
      (node (ref "JX1") (pin "P$20") (pinfunction "P$81_P$20") (pintype "bidirectional"))
    )
    (net (code "130") (name "unconnected-(JX1-P$82-PadP$19)") (class "Default")
      (node (ref "JX1") (pin "P$19") (pinfunction "P$82_P$19") (pintype "bidirectional"))
    )
    (net (code "131") (name "unconnected-(JX1-P$83-PadP$18)") (class "Default")
      (node (ref "JX1") (pin "P$18") (pinfunction "P$83_P$18") (pintype "bidirectional"))
    )
    (net (code "132") (name "unconnected-(JX1-P$84-PadP$17)") (class "Default")
      (node (ref "JX1") (pin "P$17") (pinfunction "P$84_P$17") (pintype "bidirectional"))
    )
    (net (code "133") (name "unconnected-(JX1-P$87-PadP$14)") (class "Default")
      (node (ref "JX1") (pin "P$14") (pinfunction "P$87_P$14") (pintype "bidirectional"))
    )
    (net (code "134") (name "unconnected-(JX1-P$88-PadP$13)") (class "Default")
      (node (ref "JX1") (pin "P$13") (pinfunction "P$88_P$13") (pintype "bidirectional"))
    )
    (net (code "135") (name "unconnected-(JX1-P$89-PadP$12)") (class "Default")
      (node (ref "JX1") (pin "P$12") (pinfunction "P$89_P$12") (pintype "bidirectional"))
    )
    (net (code "136") (name "unconnected-(JX1-P$90-PadP$11)") (class "Default")
      (node (ref "JX1") (pin "P$11") (pinfunction "P$90_P$11") (pintype "bidirectional"))
    )
    (net (code "137") (name "unconnected-(JX1-P$91-PadP$10)") (class "Default")
      (node (ref "JX1") (pin "P$10") (pinfunction "P$91_P$10") (pintype "bidirectional"))
    )
    (net (code "138") (name "unconnected-(JX1-P$92-PadP$9)") (class "Default")
      (node (ref "JX1") (pin "P$9") (pinfunction "P$92_P$9") (pintype "bidirectional"))
    )
    (net (code "139") (name "unconnected-(JX1-P$93-PadP$8)") (class "Default")
      (node (ref "JX1") (pin "P$8") (pinfunction "P$93_P$8") (pintype "bidirectional"))
    )
    (net (code "140") (name "unconnected-(JX1-P$94-PadP$7)") (class "Default")
      (node (ref "JX1") (pin "P$7") (pinfunction "P$94_P$7") (pintype "bidirectional"))
    )
    (net (code "141") (name "unconnected-(JX2-P$1-PadP$100)") (class "Default")
      (node (ref "JX2") (pin "P$100") (pinfunction "P$1_P$100") (pintype "bidirectional"))
    )
    (net (code "142") (name "unconnected-(JX2-P$2-PadP$99)") (class "Default")
      (node (ref "JX2") (pin "P$99") (pinfunction "P$2_P$99") (pintype "bidirectional"))
    )
    (net (code "143") (name "unconnected-(JX2-P$3-PadP$98)") (class "Default")
      (node (ref "JX2") (pin "P$98") (pinfunction "P$3_P$98") (pintype "bidirectional"))
    )
    (net (code "144") (name "unconnected-(JX2-P$4-PadP$97)") (class "Default")
      (node (ref "JX2") (pin "P$97") (pinfunction "P$4_P$97") (pintype "bidirectional"))
    )
    (net (code "145") (name "unconnected-(JX2-P$5-PadP$96)") (class "Default")
      (node (ref "JX2") (pin "P$96") (pinfunction "P$5_P$96") (pintype "bidirectional"))
    )
    (net (code "146") (name "unconnected-(JX2-P$6-PadP$95)") (class "Default")
      (node (ref "JX2") (pin "P$95") (pinfunction "P$6_P$95") (pintype "bidirectional"))
    )
    (net (code "147") (name "unconnected-(JX2-P$7-PadP$94)") (class "Default")
      (node (ref "JX2") (pin "P$94") (pinfunction "P$7_P$94") (pintype "bidirectional"))
    )
    (net (code "148") (name "unconnected-(JX2-P$8-PadP$93)") (class "Default")
      (node (ref "JX2") (pin "P$93") (pinfunction "P$8_P$93") (pintype "bidirectional"))
    )
    (net (code "149") (name "unconnected-(JX2-P$9-PadP$92)") (class "Default")
      (node (ref "JX2") (pin "P$92") (pinfunction "P$9_P$92") (pintype "bidirectional"))
    )
    (net (code "150") (name "unconnected-(JX2-P$13-PadP$88)") (class "Default")
      (node (ref "JX2") (pin "P$88") (pinfunction "P$13_P$88") (pintype "bidirectional"))
    )
    (net (code "151") (name "unconnected-(JX2-P$14-PadP$87)") (class "Default")
      (node (ref "JX2") (pin "P$87") (pinfunction "P$14_P$87") (pintype "bidirectional"))
    )
    (net (code "152") (name "unconnected-(JX2-P$18-PadP$83)") (class "Default")
      (node (ref "JX2") (pin "P$83") (pinfunction "P$18_P$83") (pintype "bidirectional"))
    )
    (net (code "153") (name "unconnected-(JX2-P$20-PadP$81)") (class "Default")
      (node (ref "JX2") (pin "P$81") (pinfunction "P$20_P$81") (pintype "bidirectional"))
    )
    (net (code "154") (name "unconnected-(JX2-P$24-PadP$77)") (class "Default")
      (node (ref "JX2") (pin "P$77") (pinfunction "P$24_P$77") (pintype "bidirectional"))
    )
    (net (code "155") (name "unconnected-(JX2-P$26-PadP$75)") (class "Default")
      (node (ref "JX2") (pin "P$75") (pinfunction "P$26_P$75") (pintype "bidirectional"))
    )
    (net (code "156") (name "unconnected-(JX2-P$30-PadP$71)") (class "Default")
      (node (ref "JX2") (pin "P$71") (pinfunction "P$30_P$71") (pintype "bidirectional"))
    )
    (net (code "157") (name "unconnected-(JX2-P$32-PadP$69)") (class "Default")
      (node (ref "JX2") (pin "P$69") (pinfunction "P$32_P$69") (pintype "bidirectional"))
    )
    (net (code "158") (name "unconnected-(JX2-P$36-PadP$65)") (class "Default")
      (node (ref "JX2") (pin "P$65") (pinfunction "P$36_P$65") (pintype "bidirectional"))
    )
    (net (code "159") (name "unconnected-(JX2-P$38-PadP$63)") (class "Default")
      (node (ref "JX2") (pin "P$63") (pinfunction "P$38_P$63") (pintype "bidirectional"))
    )
    (net (code "160") (name "unconnected-(JX2-P$42-PadP$59)") (class "Default")
      (node (ref "JX2") (pin "P$59") (pinfunction "P$42_P$59") (pintype "bidirectional"))
    )
    (net (code "161") (name "unconnected-(JX2-P$44-PadP$57)") (class "Default")
      (node (ref "JX2") (pin "P$57") (pinfunction "P$44_P$57") (pintype "bidirectional"))
    )
    (net (code "162") (name "unconnected-(JX2-P$47-PadP$54)") (class "Default")
      (node (ref "JX2") (pin "P$54") (pinfunction "P$47_P$54") (pintype "bidirectional"))
    )
    (net (code "163") (name "unconnected-(JX2-P$48-PadP$53)") (class "Default")
      (node (ref "JX2") (pin "P$53") (pinfunction "P$48_P$53") (pintype "bidirectional"))
    )
    (net (code "164") (name "unconnected-(JX2-P$49-PadP$52)") (class "Default")
      (node (ref "JX2") (pin "P$52") (pinfunction "P$49_P$52") (pintype "bidirectional"))
    )
    (net (code "165") (name "unconnected-(JX2-P$50-PadP$51)") (class "Default")
      (node (ref "JX2") (pin "P$51") (pinfunction "P$50_P$51") (pintype "bidirectional"))
    )
    (net (code "166") (name "unconnected-(JX2-P$56-PadP$45)") (class "Default")
      (node (ref "JX2") (pin "P$45") (pinfunction "P$56_P$45") (pintype "bidirectional"))
    )
    (net (code "167") (name "unconnected-(JX2-P$62-PadP$39)") (class "Default")
      (node (ref "JX2") (pin "P$39") (pinfunction "P$62_P$39") (pintype "bidirectional"))
    )
    (net (code "168") (name "unconnected-(JX2-P$64-PadP$37)") (class "Default")
      (node (ref "JX2") (pin "P$37") (pinfunction "P$64_P$37") (pintype "bidirectional"))
    )
    (net (code "169") (name "unconnected-(JX2-P$68-PadP$33)") (class "Default")
      (node (ref "JX2") (pin "P$33") (pinfunction "P$68_P$33") (pintype "bidirectional"))
    )
    (net (code "170") (name "unconnected-(JX2-P$70-PadP$31)") (class "Default")
      (node (ref "JX2") (pin "P$31") (pinfunction "P$70_P$31") (pintype "bidirectional"))
    )
    (net (code "171") (name "unconnected-(JX2-P$74-PadP$27)") (class "Default")
      (node (ref "JX2") (pin "P$27") (pinfunction "P$74_P$27") (pintype "bidirectional"))
    )
    (net (code "172") (name "unconnected-(JX2-P$76-PadP$25)") (class "Default")
      (node (ref "JX2") (pin "P$25") (pinfunction "P$76_P$25") (pintype "bidirectional"))
    )
    (net (code "173") (name "unconnected-(JX2-P$81-PadP$20)") (class "Default")
      (node (ref "JX2") (pin "P$20") (pinfunction "P$81_P$20") (pintype "bidirectional"))
    )
    (net (code "174") (name "unconnected-(JX2-P$93-PadP$8)") (class "Default")
      (node (ref "JX2") (pin "P$8") (pinfunction "P$93_P$8") (pintype "bidirectional"))
    )
    (net (code "175") (name "unconnected-(JX2-P$94-PadP$7)") (class "Default")
      (node (ref "JX2") (pin "P$7") (pinfunction "P$94_P$7") (pintype "bidirectional"))
    )
    (net (code "176") (name "unconnected-(JX2-P$95-PadP$6)") (class "Default")
      (node (ref "JX2") (pin "P$6") (pinfunction "P$95_P$6") (pintype "bidirectional"))
    )
    (net (code "177") (name "unconnected-(JX2-P$96-PadP$5)") (class "Default")
      (node (ref "JX2") (pin "P$5") (pinfunction "P$96_P$5") (pintype "bidirectional"))
    )
    (net (code "178") (name "unconnected-(JX2-P$97-PadP$4)") (class "Default")
      (node (ref "JX2") (pin "P$4") (pinfunction "P$97_P$4") (pintype "bidirectional"))
    )
    (net (code "179") (name "unconnected-(JX2-P$98-PadP$3)") (class "Default")
      (node (ref "JX2") (pin "P$3") (pinfunction "P$98_P$3") (pintype "bidirectional"))
    )
    (net (code "180") (name "unconnected-(JX2-P$99-PadP$2)") (class "Default")
      (node (ref "JX2") (pin "P$2") (pinfunction "P$99_P$2") (pintype "bidirectional"))
    )
    (net (code "181") (name "unconnected-(JX2-P$100-PadP$1)") (class "Default")
      (node (ref "JX2") (pin "P$1") (pinfunction "P$100_P$1") (pintype "bidirectional"))
    )
    (net (code "182") (name "unconnected-(U$18-~{CLK}-PadP$5)") (class "Default")
      (node (ref "U$18") (pin "P$5") (pinfunction "~{CLK}_P$5") (pintype "bidirectional"))
    )
  )
)
